# axiom_beta_sensor_cmv12000_v0_12_53e8c18.net
KiCad netlist of a schematic drawn in EAGLE
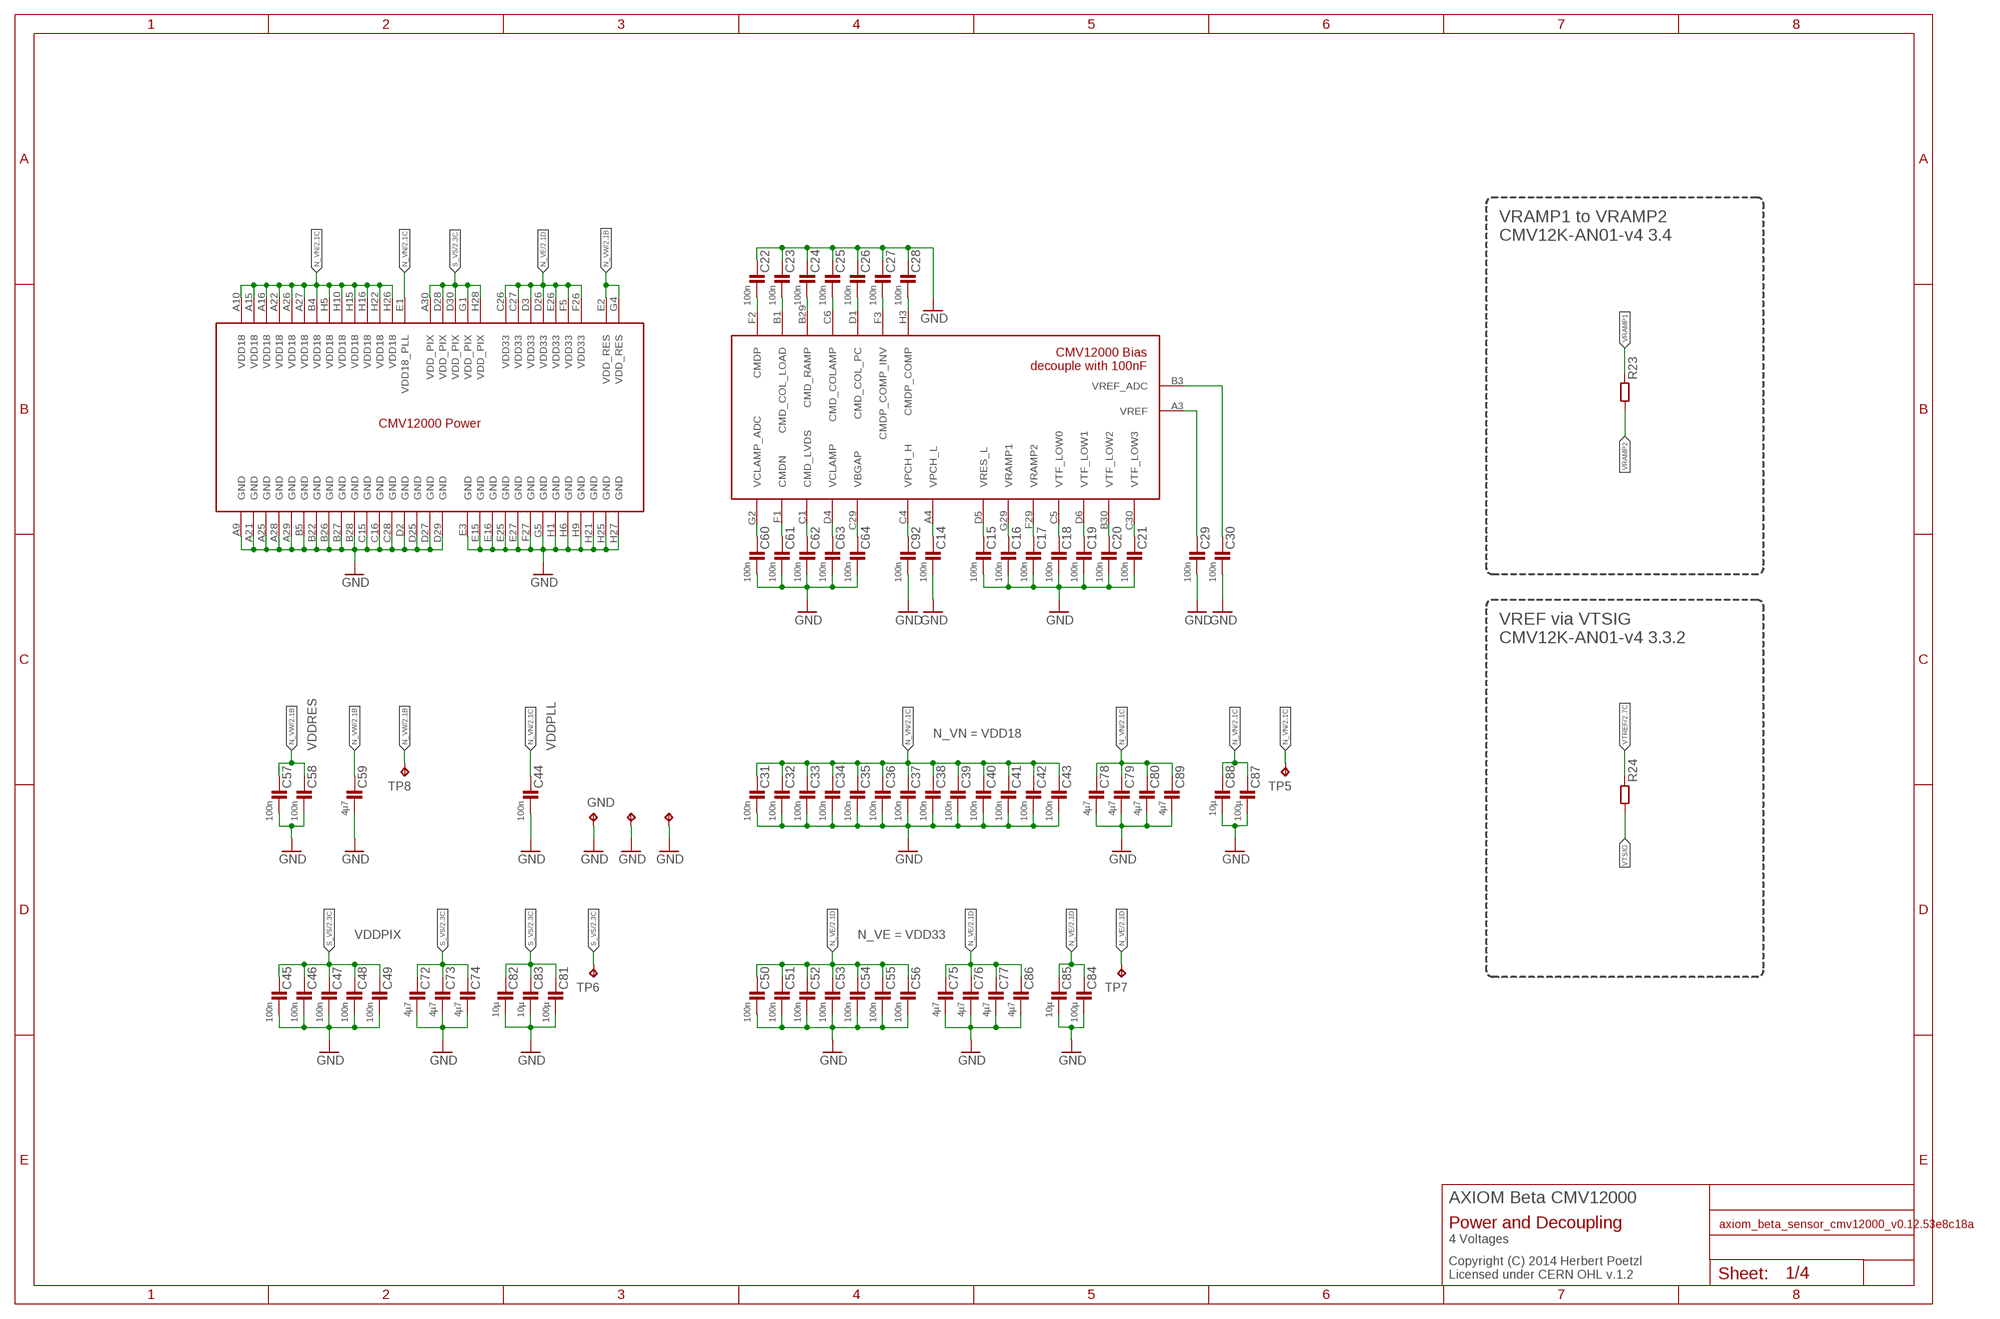
[diagram p0: schematic, sheet 1]
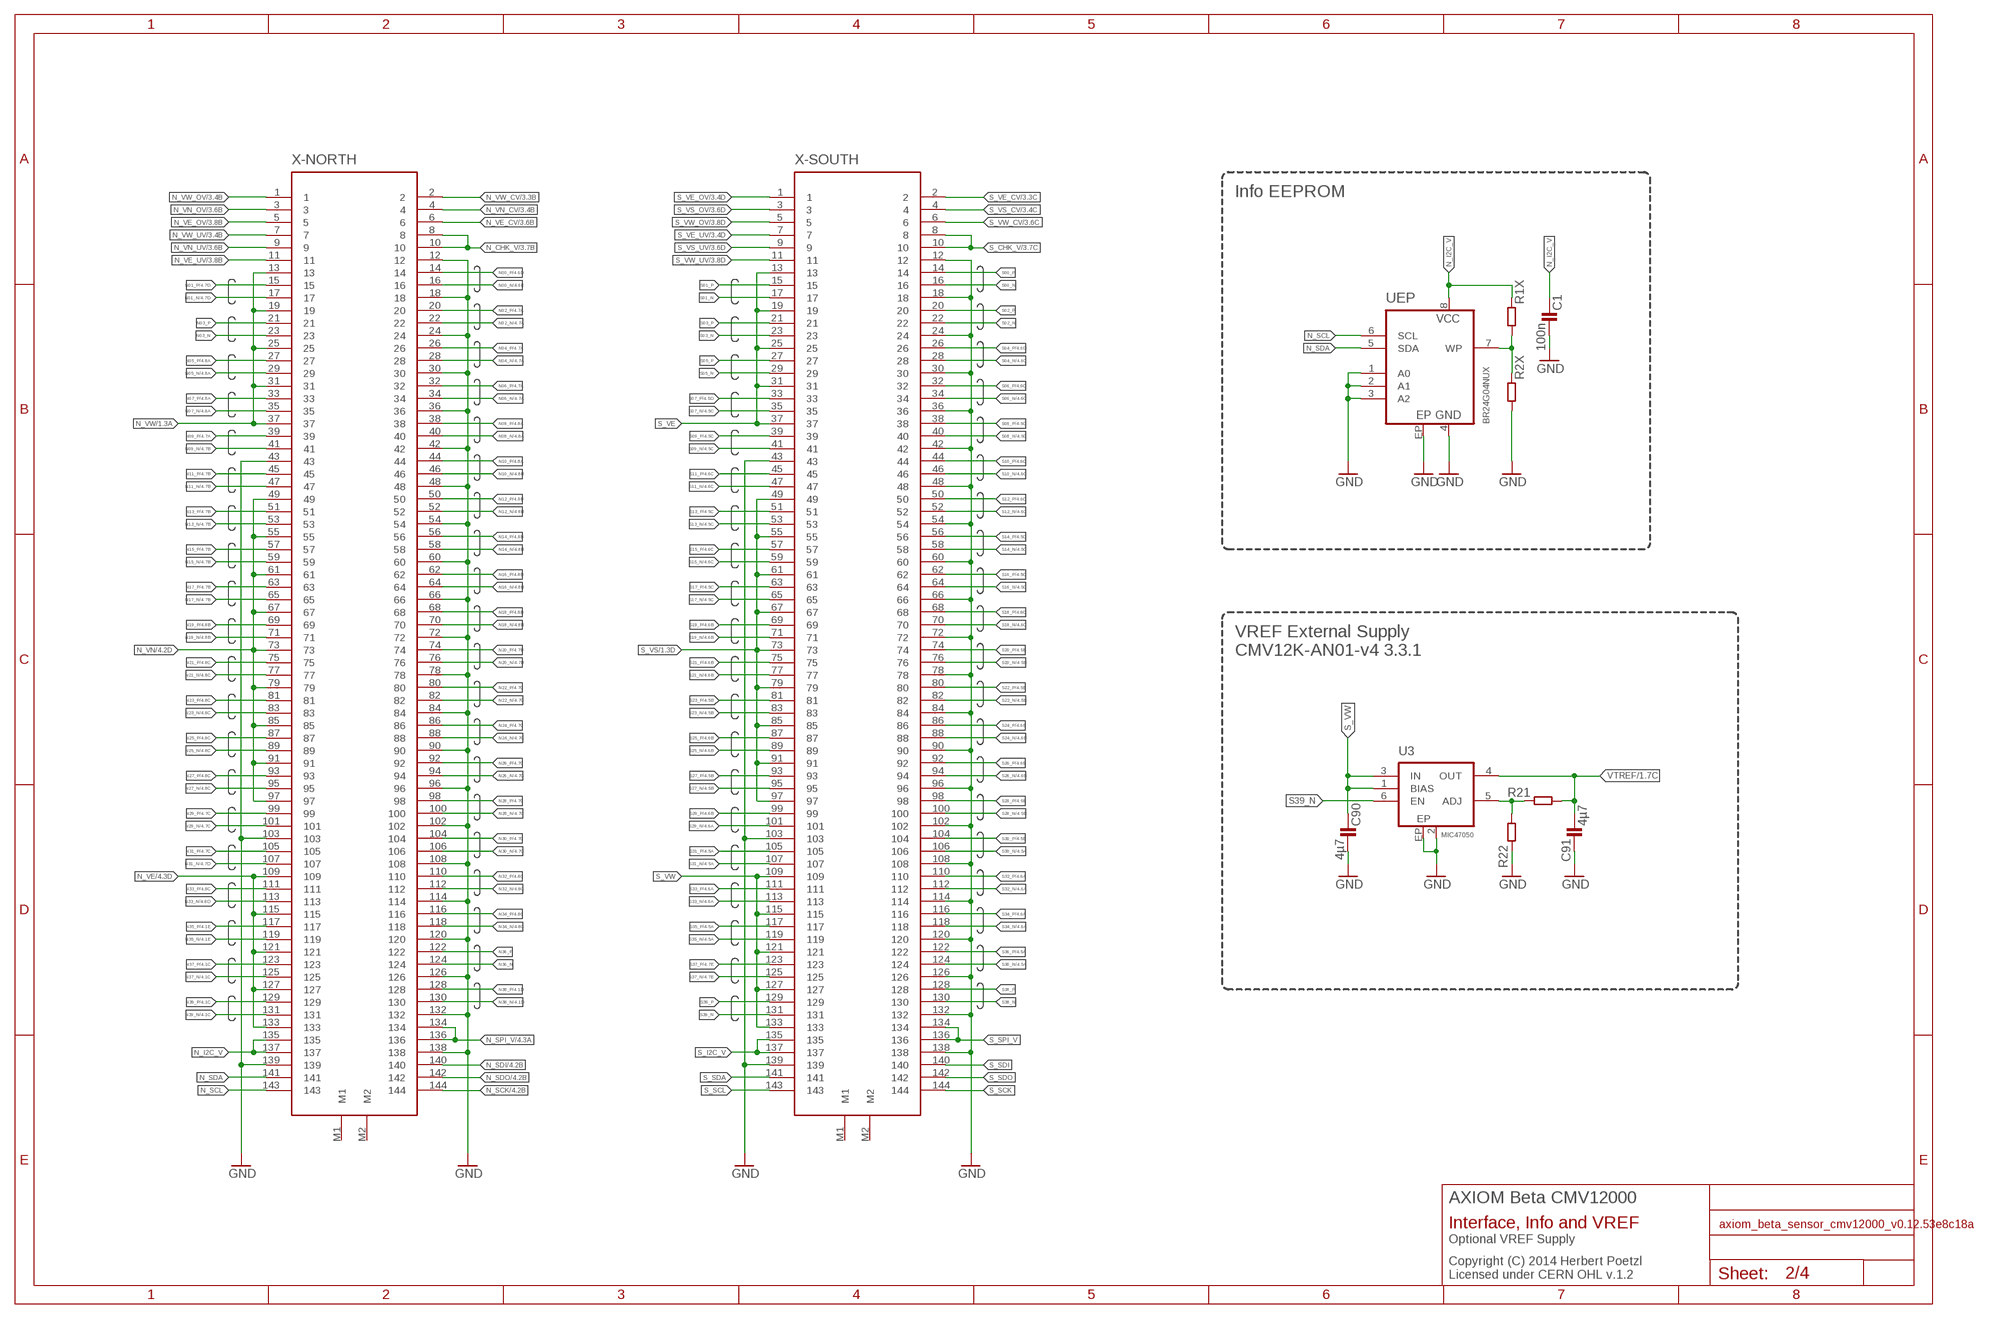
[diagram p1: schematic, sheet 2]
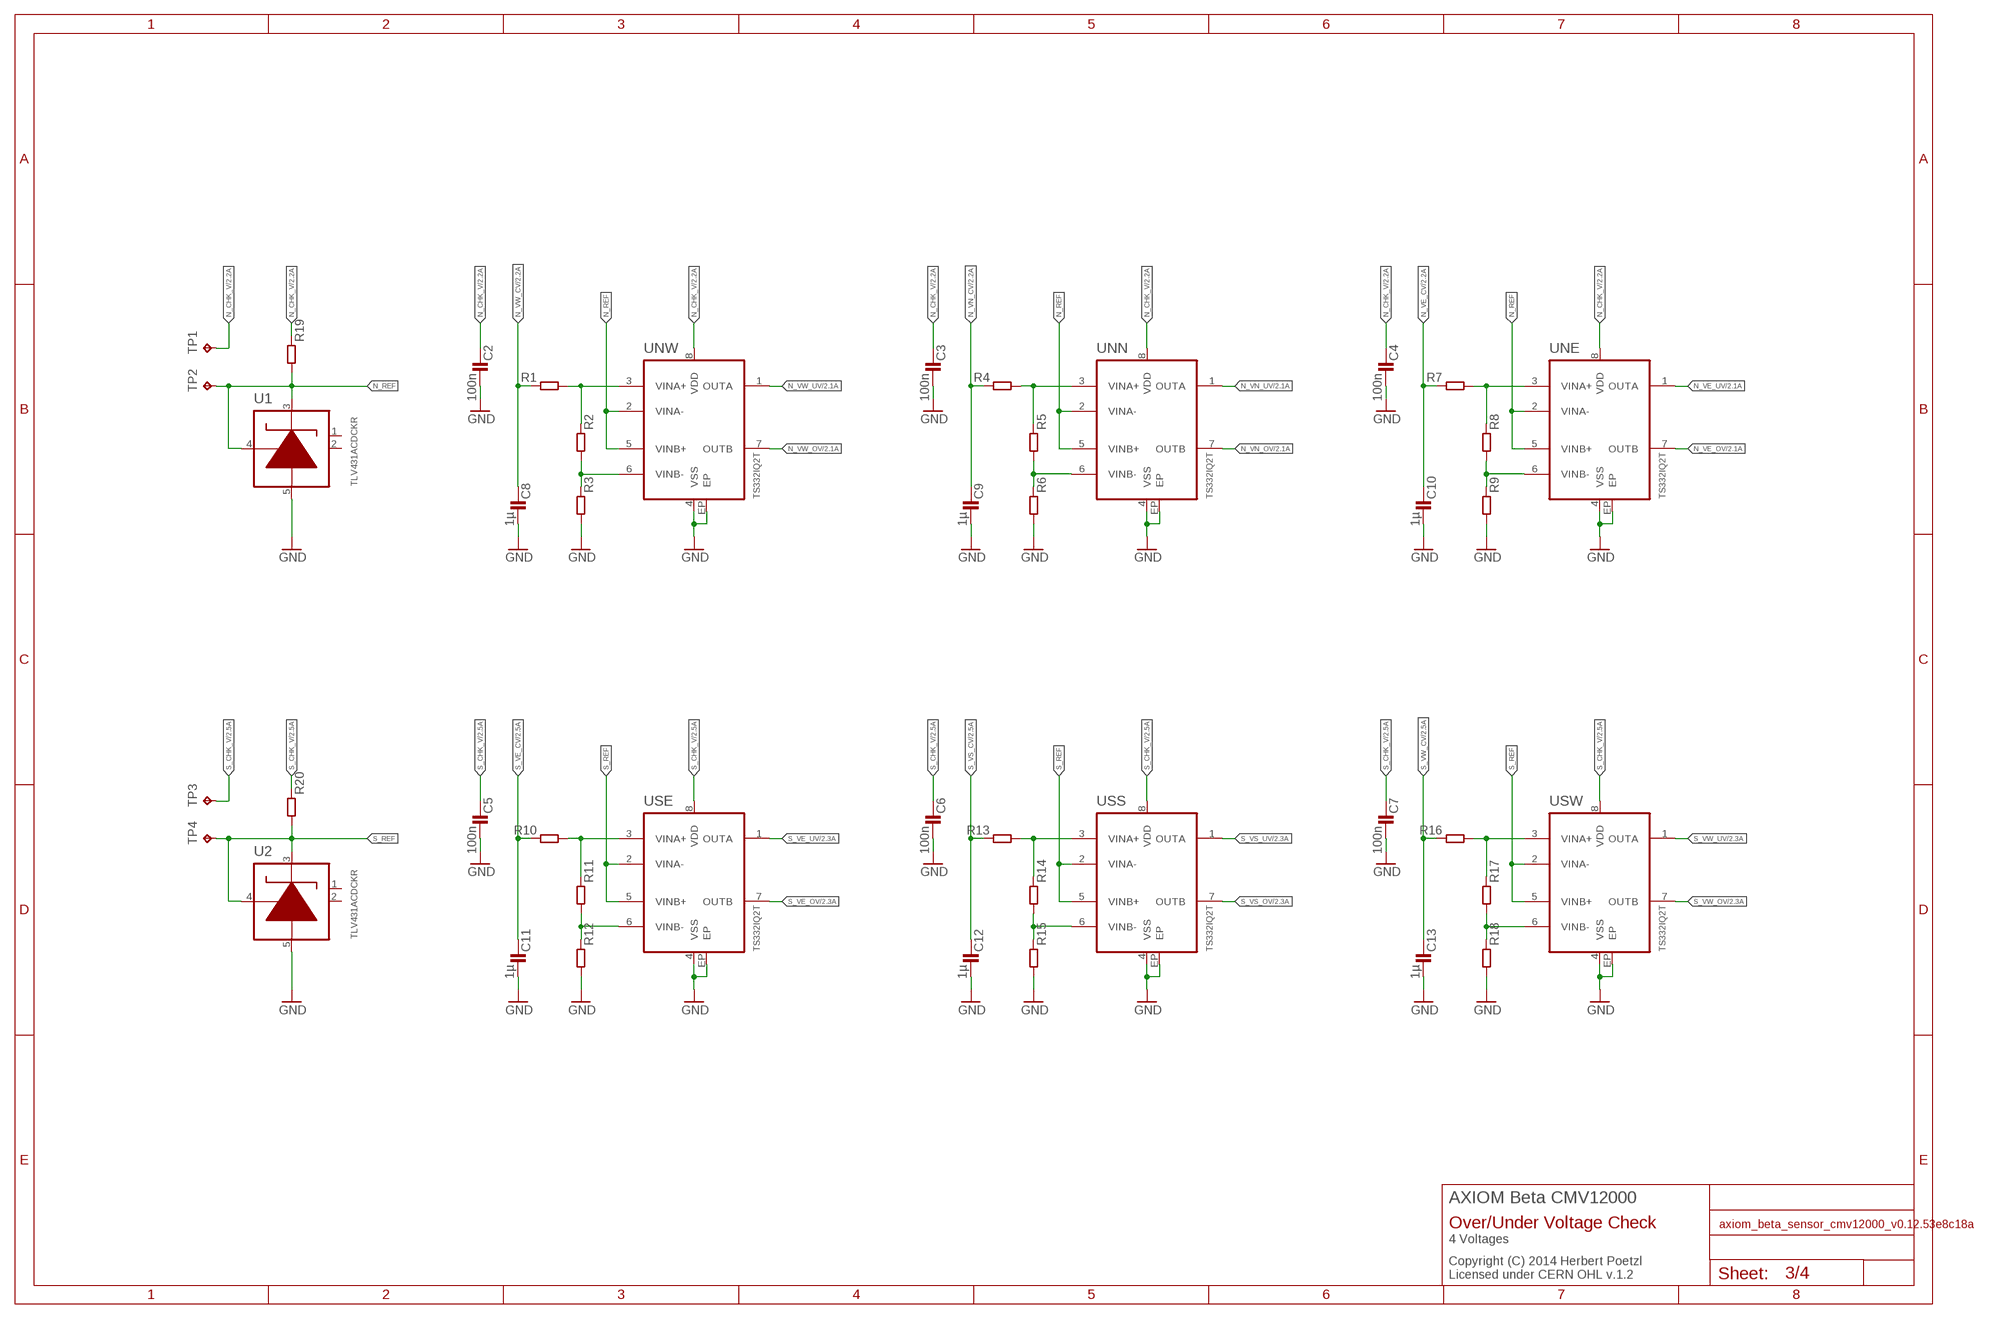
[diagram p2: schematic, sheet 3]
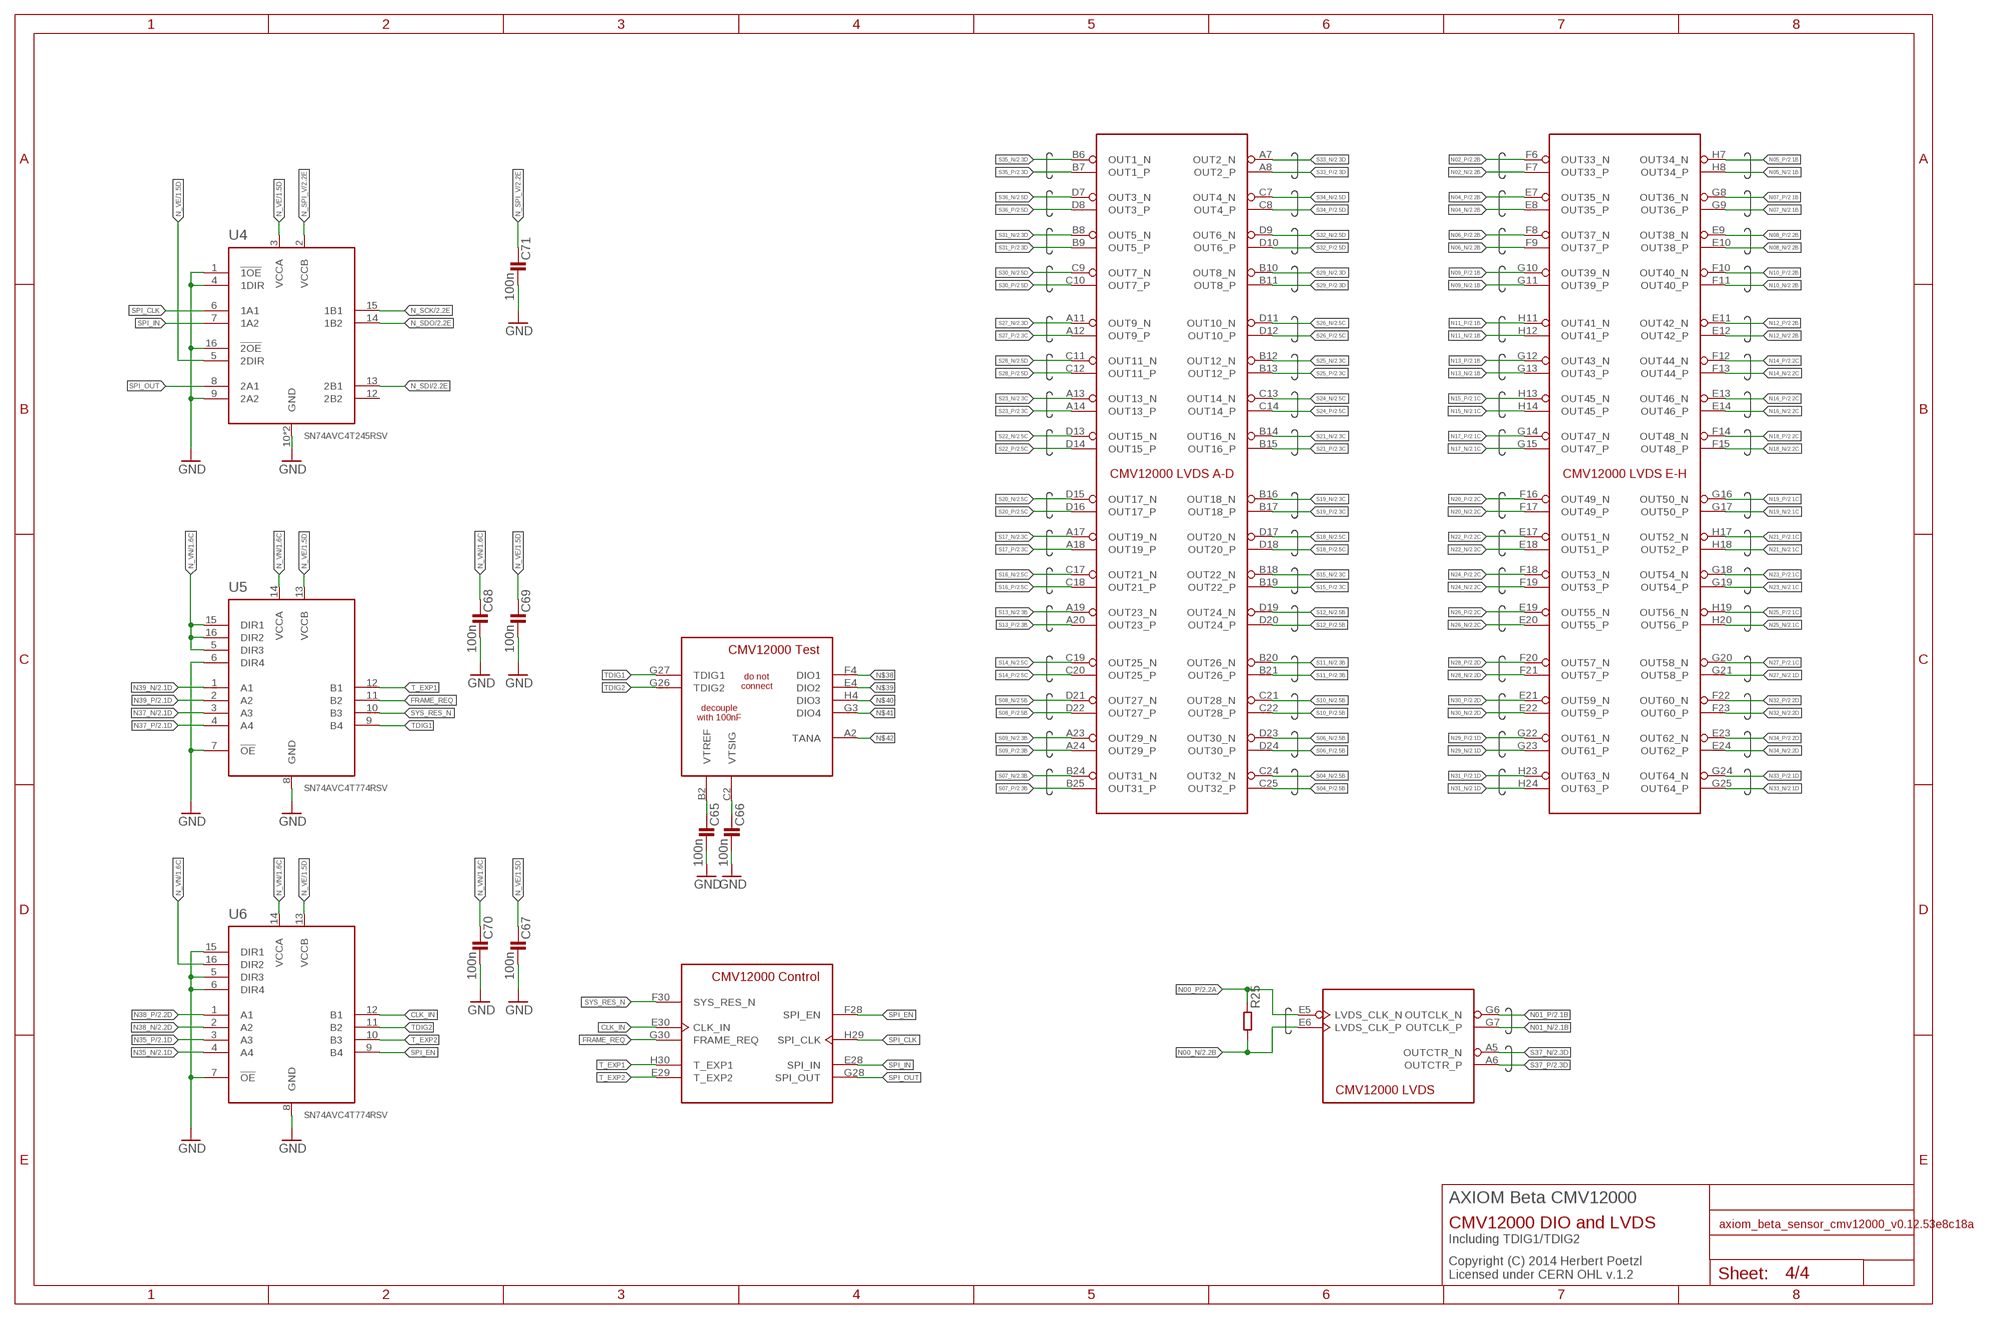
[diagram p3: schematic, sheet 4]

(export (version "E")
  (design (tool "Eeschema 10.0.6"))
  (components
    (comp (ref "C14")
      (value "100n")
      (footprint "eagle-import:0402-C")
      (libsource (lib "eagle-import") (part "C0402-C"))
    )
    (comp (ref "C15")
      (value "100n")
      (footprint "eagle-import:0402-C")
      (libsource (lib "eagle-import") (part "C0402-C"))
    )
    (comp (ref "C16")
      (value "100n")
      (footprint "eagle-import:0402-C")
      (libsource (lib "eagle-import") (part "C0402-C"))
    )
    (comp (ref "C17")
      (value "100n")
      (footprint "eagle-import:0402-C")
      (libsource (lib "eagle-import") (part "C0402-C"))
    )
    (comp (ref "C18")
      (value "100n")
      (footprint "eagle-import:0402-C")
      (libsource (lib "eagle-import") (part "C0402-C"))
    )
    (comp (ref "C19")
      (value "100n")
      (footprint "eagle-import:0402-C")
      (libsource (lib "eagle-import") (part "C0402-C"))
    )
    (comp (ref "C20")
      (value "100n")
      (footprint "eagle-import:0402-C")
      (libsource (lib "eagle-import") (part "C0402-C"))
    )
    (comp (ref "C21")
      (value "100n")
      (footprint "eagle-import:0402-C")
      (libsource (lib "eagle-import") (part "C0402-C"))
    )
    (comp (ref "C22")
      (value "100n")
      (footprint "eagle-import:0402-C")
      (libsource (lib "eagle-import") (part "C0402-C"))
    )
    (comp (ref "C23")
      (value "100n")
      (footprint "eagle-import:0402-C")
      (libsource (lib "eagle-import") (part "C0402-C"))
    )
    (comp (ref "C24")
      (value "100n")
      (footprint "eagle-import:0402-C")
      (libsource (lib "eagle-import") (part "C0402-C"))
    )
    (comp (ref "C25")
      (value "100n")
      (footprint "eagle-import:0402-C")
      (libsource (lib "eagle-import") (part "C0402-C"))
    )
    (comp (ref "C26")
      (value "100n")
      (footprint "eagle-import:0402-C")
      (libsource (lib "eagle-import") (part "C0402-C"))
    )
    (comp (ref "C27")
      (value "100n")
      (footprint "eagle-import:0402-C")
      (libsource (lib "eagle-import") (part "C0402-C"))
    )
    (comp (ref "C28")
      (value "100n")
      (footprint "eagle-import:0402-C")
      (libsource (lib "eagle-import") (part "C0402-C"))
    )
    (comp (ref "C29")
      (value "100n")
      (footprint "eagle-import:0402-C")
      (libsource (lib "eagle-import") (part "C0402-C"))
    )
    (comp (ref "C30")
      (value "100n")
      (footprint "eagle-import:0402-C")
      (libsource (lib "eagle-import") (part "C0402-C"))
    )
    (comp (ref "C31")
      (value "100n")
      (footprint "eagle-import:0402-C")
      (libsource (lib "eagle-import") (part "C0402-C"))
    )
    (comp (ref "C32")
      (value "100n")
      (footprint "eagle-import:0402-C")
      (libsource (lib "eagle-import") (part "C0402-C"))
    )
    (comp (ref "C33")
      (value "100n")
      (footprint "eagle-import:0402-C")
      (libsource (lib "eagle-import") (part "C0402-C"))
    )
    (comp (ref "C34")
      (value "100n")
      (footprint "eagle-import:0402-C")
      (libsource (lib "eagle-import") (part "C0402-C"))
    )
    (comp (ref "C35")
      (value "100n")
      (footprint "eagle-import:0402-C")
      (libsource (lib "eagle-import") (part "C0402-C"))
    )
    (comp (ref "C36")
      (value "100n")
      (footprint "eagle-import:0402-C")
      (libsource (lib "eagle-import") (part "C0402-C"))
    )
    (comp (ref "C37")
      (value "100n")
      (footprint "eagle-import:0402-C")
      (libsource (lib "eagle-import") (part "C0402-C"))
    )
    (comp (ref "C38")
      (value "100n")
      (footprint "eagle-import:0402-C")
      (libsource (lib "eagle-import") (part "C0402-C"))
    )
    (comp (ref "C39")
      (value "100n")
      (footprint "eagle-import:0402-C")
      (libsource (lib "eagle-import") (part "C0402-C"))
    )
    (comp (ref "C40")
      (value "100n")
      (footprint "eagle-import:0402-C")
      (libsource (lib "eagle-import") (part "C0402-C"))
    )
    (comp (ref "C41")
      (value "100n")
      (footprint "eagle-import:0402-C")
      (libsource (lib "eagle-import") (part "C0402-C"))
    )
    (comp (ref "C42")
      (value "100n")
      (footprint "eagle-import:0402-C")
      (libsource (lib "eagle-import") (part "C0402-C"))
    )
    (comp (ref "C43")
      (value "100n")
      (footprint "eagle-import:0402-C")
      (libsource (lib "eagle-import") (part "C0402-C"))
    )
    (comp (ref "C44")
      (value "100n")
      (footprint "eagle-import:0402-C")
      (libsource (lib "eagle-import") (part "C0402-C"))
    )
    (comp (ref "C45")
      (value "100n")
      (footprint "eagle-import:0402-C")
      (libsource (lib "eagle-import") (part "C0402-C"))
    )
    (comp (ref "C46")
      (value "100n")
      (footprint "eagle-import:0402-C")
      (libsource (lib "eagle-import") (part "C0402-C"))
    )
    (comp (ref "C47")
      (value "100n")
      (footprint "eagle-import:0402-C")
      (libsource (lib "eagle-import") (part "C0402-C"))
    )
    (comp (ref "C48")
      (value "100n")
      (footprint "eagle-import:0402-C")
      (libsource (lib "eagle-import") (part "C0402-C"))
    )
    (comp (ref "C49")
      (value "100n")
      (footprint "eagle-import:0402-C")
      (libsource (lib "eagle-import") (part "C0402-C"))
    )
    (comp (ref "C50")
      (value "100n")
      (footprint "eagle-import:0402-C")
      (libsource (lib "eagle-import") (part "C0402-C"))
    )
    (comp (ref "C51")
      (value "100n")
      (footprint "eagle-import:0402-C")
      (libsource (lib "eagle-import") (part "C0402-C"))
    )
    (comp (ref "C52")
      (value "100n")
      (footprint "eagle-import:0402-C")
      (libsource (lib "eagle-import") (part "C0402-C"))
    )
    (comp (ref "C53")
      (value "100n")
      (footprint "eagle-import:0402-C")
      (libsource (lib "eagle-import") (part "C0402-C"))
    )
    (comp (ref "C54")
      (value "100n")
      (footprint "eagle-import:0402-C")
      (libsource (lib "eagle-import") (part "C0402-C"))
    )
    (comp (ref "C55")
      (value "100n")
      (footprint "eagle-import:0402-C")
      (libsource (lib "eagle-import") (part "C0402-C"))
    )
    (comp (ref "C56")
      (value "100n")
      (footprint "eagle-import:0402-C")
      (libsource (lib "eagle-import") (part "C0402-C"))
    )
    (comp (ref "C57")
      (value "100n")
      (footprint "eagle-import:0402-C")
      (libsource (lib "eagle-import") (part "C0402-C"))
    )
    (comp (ref "C58")
      (value "100n")
      (footprint "eagle-import:0402-C")
      (libsource (lib "eagle-import") (part "C0402-C"))
    )
    (comp (ref "C59")
      (value "4µ7")
      (footprint "eagle-import:0402-C")
      (libsource (lib "eagle-import") (part "C0402-C"))
    )
    (comp (ref "C60")
      (value "100n")
      (footprint "eagle-import:0402-C")
      (libsource (lib "eagle-import") (part "C0402-C"))
    )
    (comp (ref "C61")
      (value "100n")
      (footprint "eagle-import:0402-C")
      (libsource (lib "eagle-import") (part "C0402-C"))
    )
    (comp (ref "C62")
      (value "100n")
      (footprint "eagle-import:0402-C")
      (libsource (lib "eagle-import") (part "C0402-C"))
    )
    (comp (ref "C63")
      (value "100n")
      (footprint "eagle-import:0402-C")
      (libsource (lib "eagle-import") (part "C0402-C"))
    )
    (comp (ref "C64")
      (value "100n")
      (footprint "eagle-import:0402-C")
      (libsource (lib "eagle-import") (part "C0402-C"))
    )
    (comp (ref "C72")
      (value "4µ7")
      (footprint "eagle-import:0402-B")
      (libsource (lib "eagle-import") (part "C0402-B"))
    )
    (comp (ref "C73")
      (value "4µ7")
      (footprint "eagle-import:0402-C")
      (libsource (lib "eagle-import") (part "C0402-C"))
    )
    (comp (ref "C74")
      (value "4µ7")
      (footprint "eagle-import:0402-C")
      (libsource (lib "eagle-import") (part "C0402-C"))
    )
    (comp (ref "C75")
      (value "4µ7")
      (footprint "eagle-import:0402-C")
      (libsource (lib "eagle-import") (part "C0402-C"))
    )
    (comp (ref "C76")
      (value "4µ7")
      (footprint "eagle-import:0402-C")
      (libsource (lib "eagle-import") (part "C0402-C"))
    )
    (comp (ref "C77")
      (value "4µ7")
      (footprint "eagle-import:0402-B")
      (libsource (lib "eagle-import") (part "C0402-B"))
    )
    (comp (ref "C78")
      (value "4µ7")
      (footprint "eagle-import:0402-B")
      (libsource (lib "eagle-import") (part "C0402-B"))
    )
    (comp (ref "C79")
      (value "4µ7")
      (footprint "eagle-import:0402-C")
      (libsource (lib "eagle-import") (part "C0402-C"))
    )
    (comp (ref "C80")
      (value "4µ7")
      (footprint "eagle-import:0402-C")
      (libsource (lib "eagle-import") (part "C0402-C"))
    )
    (comp (ref "C81")
      (value "100µ")
      (footprint "eagle-import:1206-B")
      (libsource (lib "eagle-import") (part "C1206-B"))
    )
    (comp (ref "C82")
      (value "10µ")
      (footprint "eagle-import:0603-C")
      (libsource (lib "eagle-import") (part "C0603-C"))
    )
    (comp (ref "C83")
      (value "10µ")
      (footprint "eagle-import:0603-C")
      (libsource (lib "eagle-import") (part "C0603-C"))
    )
    (comp (ref "C84")
      (value "100µ")
      (footprint "eagle-import:1206-B")
      (libsource (lib "eagle-import") (part "C1206-B"))
    )
    (comp (ref "C85")
      (value "10µ")
      (footprint "eagle-import:0603-C")
      (libsource (lib "eagle-import") (part "C0603-C"))
    )
    (comp (ref "C86")
      (value "4µ7")
      (footprint "eagle-import:0402-C")
      (libsource (lib "eagle-import") (part "C0402-C"))
    )
    (comp (ref "C87")
      (value "100µ")
      (footprint "eagle-import:1206-B")
      (libsource (lib "eagle-import") (part "C1206-B"))
    )
    (comp (ref "C88")
      (value "10µ")
      (footprint "eagle-import:0603-C")
      (libsource (lib "eagle-import") (part "C0603-C"))
    )
    (comp (ref "C89")
      (value "4µ7")
      (footprint "eagle-import:0402-C")
      (libsource (lib "eagle-import") (part "C0402-C"))
    )
    (comp (ref "C92")
      (value "100n")
      (footprint "eagle-import:0402-C")
      (libsource (lib "eagle-import") (part "C0402-C"))
    )
    (comp (ref "GND")
      (value "TPTP10R")
      (footprint "eagle-import:TP10R")
      (libsource (lib "eagle-import") (part "TPTP10R"))
    )
    (comp (ref "GND75")
      (value "TPTP10R")
      (footprint "eagle-import:TP10R")
      (libsource (lib "eagle-import") (part "TPTP10R"))
    )
    (comp (ref "GND77")
      (value "TPTP10R")
      (footprint "eagle-import:TP10R")
      (libsource (lib "eagle-import") (part "TPTP10R"))
    )
    (comp (ref "R23")
      (value "R0402-C")
      (footprint "eagle-import:0402-C")
      (libsource (lib "eagle-import") (part "R0402-C"))
    )
    (comp (ref "R24")
      (value "R0402-C")
      (footprint "eagle-import:0402-C")
      (libsource (lib "eagle-import") (part "R0402-C"))
    )
    (comp (ref "SENSOR")
      (value "CMV12000ANDON")
      (footprint "eagle-import:10-30-07-237-400T4")
      (libsource (lib "eagle-import") (part "CMV12000ANDON"))
    )
    (comp (ref "TP5")
      (value "TPTP10R")
      (footprint "eagle-import:TP10R")
      (libsource (lib "eagle-import") (part "TPTP10R"))
    )
    (comp (ref "TP6")
      (value "TPTP10R")
      (footprint "eagle-import:TP10R")
      (libsource (lib "eagle-import") (part "TPTP10R"))
    )
    (comp (ref "TP7")
      (value "TPTP10R")
      (footprint "eagle-import:TP10R")
      (libsource (lib "eagle-import") (part "TPTP10R"))
    )
    (comp (ref "TP8")
      (value "TPTP10R")
      (footprint "eagle-import:TP10R")
      (libsource (lib "eagle-import") (part "TPTP10R"))
    )
    (comp (ref "C65")
      (value "100n")
      (footprint "eagle-import:0402-C")
      (libsource (lib "eagle-import") (part "C0402-C"))
    )
    (comp (ref "C66")
      (value "100n")
      (footprint "eagle-import:0402-C")
      (libsource (lib "eagle-import") (part "C0402-C"))
    )
    (comp (ref "C67")
      (value "100n")
      (footprint "eagle-import:0402-C")
      (libsource (lib "eagle-import") (part "C0402-C"))
    )
    (comp (ref "C68")
      (value "100n")
      (footprint "eagle-import:0402-C")
      (libsource (lib "eagle-import") (part "C0402-C"))
    )
    (comp (ref "C69")
      (value "100n")
      (footprint "eagle-import:0402-C")
      (libsource (lib "eagle-import") (part "C0402-C"))
    )
    (comp (ref "C70")
      (value "100n")
      (footprint "eagle-import:0402-C")
      (libsource (lib "eagle-import") (part "C0402-C"))
    )
    (comp (ref "C71")
      (value "100n")
      (footprint "eagle-import:0402-C")
      (libsource (lib "eagle-import") (part "C0402-C"))
    )
    (comp (ref "R25")
      (value "R0402-C")
      (footprint "eagle-import:0402-C")
      (libsource (lib "eagle-import") (part "R0402-C"))
    )
    (comp (ref "U4")
      (value "SN74AVC4T245RSV")
      (footprint "eagle-import:QFN40P185X265X55-16N")
      (libsource (lib "eagle-import") (part "SN74AVC4T245RSV"))
    )
    (comp (ref "U5")
      (value "SN74AVC4T774RSV")
      (footprint "eagle-import:QFN40P185X265X55-16N")
      (libsource (lib "eagle-import") (part "SN74AVC4T774RSV"))
    )
    (comp (ref "U6")
      (value "SN74AVC4T774RSV")
      (footprint "eagle-import:QFN40P185X265X55-16N")
      (libsource (lib "eagle-import") (part "SN74AVC4T774RSV"))
    )
    (comp (ref "C1")
      (value "100n")
      (footprint "eagle-import:0402-C")
      (libsource (lib "eagle-import") (part "C0402-C"))
    )
    (comp (ref "C90")
      (value "4µ7")
      (footprint "eagle-import:0402-C")
      (libsource (lib "eagle-import") (part "C0402-C"))
    )
    (comp (ref "C91")
      (value "4µ7")
      (footprint "eagle-import:0402-C")
      (libsource (lib "eagle-import") (part "C0402-C"))
    )
    (comp (ref "R1X")
      (value "R0402-C")
      (footprint "eagle-import:0402-C")
      (libsource (lib "eagle-import") (part "R0402-C"))
    )
    (comp (ref "R2X")
      (value "R0402-C")
      (footprint "eagle-import:0402-C")
      (libsource (lib "eagle-import") (part "R0402-C"))
    )
    (comp (ref "R21")
      (value "R0402-C")
      (footprint "eagle-import:0402-C")
      (libsource (lib "eagle-import") (part "R0402-C"))
    )
    (comp (ref "R22")
      (value "R0402-C")
      (footprint "eagle-import:0402-C")
      (libsource (lib "eagle-import") (part "R0402-C"))
    )
    (comp (ref "U3")
      (value "MIC47050")
      (footprint "eagle-import:MLF-6")
      (libsource (lib "eagle-import") (part "MIC47050-ADJ"))
    )
    (comp (ref "UEP")
      (value "BR24G04NUX")
      (footprint "eagle-import:DFN200X300X100-9N")
      (libsource (lib "eagle-import") (part "BR24G04NUX"))
    )
    (comp (ref "X-NORTH")
      (value "FX10-144P")
      (footprint "eagle-import:FX10A-144P")
      (libsource (lib "eagle-import") (part "FX10-144P"))
    )
    (comp (ref "X-SOUTH")
      (value "FX10-144P")
      (footprint "eagle-import:FX10A-144P")
      (libsource (lib "eagle-import") (part "FX10-144P"))
    )
    (comp (ref "C2")
      (value "100n")
      (footprint "eagle-import:0402-C")
      (libsource (lib "eagle-import") (part "C0402-C"))
    )
    (comp (ref "C3")
      (value "100n")
      (footprint "eagle-import:0402-C")
      (libsource (lib "eagle-import") (part "C0402-C"))
    )
    (comp (ref "C4")
      (value "100n")
      (footprint "eagle-import:0402-C")
      (libsource (lib "eagle-import") (part "C0402-C"))
    )
    (comp (ref "C5")
      (value "100n")
      (footprint "eagle-import:0402-C")
      (libsource (lib "eagle-import") (part "C0402-C"))
    )
    (comp (ref "C6")
      (value "100n")
      (footprint "eagle-import:0402-C")
      (libsource (lib "eagle-import") (part "C0402-C"))
    )
    (comp (ref "C7")
      (value "100n")
      (footprint "eagle-import:0402-C")
      (libsource (lib "eagle-import") (part "C0402-C"))
    )
    (comp (ref "C8")
      (value "1µ")
      (footprint "eagle-import:0402-C")
      (libsource (lib "eagle-import") (part "C0402-C"))
    )
    (comp (ref "C9")
      (value "1µ")
      (footprint "eagle-import:0402-C")
      (libsource (lib "eagle-import") (part "C0402-C"))
    )
    (comp (ref "C10")
      (value "1µ")
      (footprint "eagle-import:0402-C")
      (libsource (lib "eagle-import") (part "C0402-C"))
    )
    (comp (ref "C11")
      (value "1µ")
      (footprint "eagle-import:0402-C")
      (libsource (lib "eagle-import") (part "C0402-C"))
    )
    (comp (ref "C12")
      (value "1µ")
      (footprint "eagle-import:0402-C")
      (libsource (lib "eagle-import") (part "C0402-C"))
    )
    (comp (ref "C13")
      (value "1µ")
      (footprint "eagle-import:0402-C")
      (libsource (lib "eagle-import") (part "C0402-C"))
    )
    (comp (ref "R1")
      (value "R0402-C")
      (footprint "eagle-import:0402-C")
      (libsource (lib "eagle-import") (part "R0402-C"))
    )
    (comp (ref "R2")
      (value "R0402-C")
      (footprint "eagle-import:0402-C")
      (libsource (lib "eagle-import") (part "R0402-C"))
    )
    (comp (ref "R3")
      (value "R0402-C")
      (footprint "eagle-import:0402-C")
      (libsource (lib "eagle-import") (part "R0402-C"))
    )
    (comp (ref "R4")
      (value "R0402-C")
      (footprint "eagle-import:0402-C")
      (libsource (lib "eagle-import") (part "R0402-C"))
    )
    (comp (ref "R5")
      (value "R0402-C")
      (footprint "eagle-import:0402-C")
      (libsource (lib "eagle-import") (part "R0402-C"))
    )
    (comp (ref "R6")
      (value "R0402-C")
      (footprint "eagle-import:0402-C")
      (libsource (lib "eagle-import") (part "R0402-C"))
    )
    (comp (ref "R7")
      (value "R0402-C")
      (footprint "eagle-import:0402-C")
      (libsource (lib "eagle-import") (part "R0402-C"))
    )
    (comp (ref "R8")
      (value "R0402-C")
      (footprint "eagle-import:0402-C")
      (libsource (lib "eagle-import") (part "R0402-C"))
    )
    (comp (ref "R9")
      (value "R0402-C")
      (footprint "eagle-import:0402-C")
      (libsource (lib "eagle-import") (part "R0402-C"))
    )
    (comp (ref "R10")
      (value "R0402-C")
      (footprint "eagle-import:0402-C")
      (libsource (lib "eagle-import") (part "R0402-C"))
    )
    (comp (ref "R11")
      (value "R0402-C")
      (footprint "eagle-import:0402-C")
      (libsource (lib "eagle-import") (part "R0402-C"))
    )
    (comp (ref "R12")
      (value "R0402-C")
      (footprint "eagle-import:0402-C")
      (libsource (lib "eagle-import") (part "R0402-C"))
    )
    (comp (ref "R13")
      (value "R0402-C")
      (footprint "eagle-import:0402-C")
      (libsource (lib "eagle-import") (part "R0402-C"))
    )
    (comp (ref "R14")
      (value "R0402-C")
      (footprint "eagle-import:0402-C")
      (libsource (lib "eagle-import") (part "R0402-C"))
    )
    (comp (ref "R15")
      (value "R0402-C")
      (footprint "eagle-import:0402-C")
      (libsource (lib "eagle-import") (part "R0402-C"))
    )
    (comp (ref "R16")
      (value "R0402-C")
      (footprint "eagle-import:0402-C")
      (libsource (lib "eagle-import") (part "R0402-C"))
    )
    (comp (ref "R17")
      (value "R0402-C")
      (footprint "eagle-import:0402-C")
      (libsource (lib "eagle-import") (part "R0402-C"))
    )
    (comp (ref "R18")
      (value "R0402-C")
      (footprint "eagle-import:0402-C")
      (libsource (lib "eagle-import") (part "R0402-C"))
    )
    (comp (ref "R19")
      (value "R0402-C")
      (footprint "eagle-import:0402-C")
      (libsource (lib "eagle-import") (part "R0402-C"))
    )
    (comp (ref "R20")
      (value "R0402-C")
      (footprint "eagle-import:0402-C")
      (libsource (lib "eagle-import") (part "R0402-C"))
    )
    (comp (ref "TP1")
      (value "TPTP10R")
      (footprint "eagle-import:TP10R")
      (libsource (lib "eagle-import") (part "TPTP10R"))
    )
    (comp (ref "TP2")
      (value "TPTP10R")
      (footprint "eagle-import:TP10R")
      (libsource (lib "eagle-import") (part "TPTP10R"))
    )
    (comp (ref "TP3")
      (value "TPTP10R")
      (footprint "eagle-import:TP10R")
      (libsource (lib "eagle-import") (part "TPTP10R"))
    )
    (comp (ref "TP4")
      (value "TPTP10R")
      (footprint "eagle-import:TP10R")
      (libsource (lib "eagle-import") (part "TPTP10R"))
    )
    (comp (ref "U1")
      (value "TLV431ACDCKR")
      (footprint "eagle-import:SOT65P210X110-5N")
      (libsource (lib "eagle-import") (part "TLV431ACDCKR"))
    )
    (comp (ref "U2")
      (value "TLV431ACDCKR")
      (footprint "eagle-import:SOT65P210X110-5N")
      (libsource (lib "eagle-import") (part "TLV431ACDCKR"))
    )
    (comp (ref "UNE")
      (value "TS332IQ2T")
      (footprint "eagle-import:DFN200X200X100-9N")
      (libsource (lib "eagle-import") (part "TS332IQ2T"))
    )
    (comp (ref "UNN")
      (value "TS332IQ2T")
      (footprint "eagle-import:DFN200X200X100-9N")
      (libsource (lib "eagle-import") (part "TS332IQ2T"))
    )
    (comp (ref "UNW")
      (value "TS332IQ2T")
      (footprint "eagle-import:DFN200X200X100-9N")
      (libsource (lib "eagle-import") (part "TS332IQ2T"))
    )
    (comp (ref "USE")
      (value "TS332IQ2T")
      (footprint "eagle-import:DFN200X200X100-9N")
      (libsource (lib "eagle-import") (part "TS332IQ2T"))
    )
    (comp (ref "USS")
      (value "TS332IQ2T")
      (footprint "eagle-import:DFN200X200X100-9N")
      (libsource (lib "eagle-import") (part "TS332IQ2T"))
    )
    (comp (ref "USW")
      (value "TS332IQ2T")
      (footprint "eagle-import:DFN200X200X100-9N")
      (libsource (lib "eagle-import") (part "TS332IQ2T"))
    )
  )
  (nets
    (net (code "1") (name "CLK_IN") (class "Default")
      (node (ref "SENSOR") (pin "E30") (pinfunction "CLK_IN_E30") (pintype "input"))
      (node (ref "U6") (pin "12") (pinfunction "B1_12") (pintype "bidirectional"))
    )
    (net (code "2") (name "FRAME_REQ") (class "Default")
      (node (ref "SENSOR") (pin "G30") (pinfunction "FRAME_REQ_G30") (pintype "input"))
      (node (ref "U5") (pin "11") (pinfunction "B2_11") (pintype "bidirectional"))
    )
    (net (code "3") (name "GND") (class "Default")
      (node (ref "C1") (pin "2") (pinfunction "2_2") (pintype "passive"))
      (node (ref "C10") (pin "2") (pinfunction "2_2") (pintype "passive"))
      (node (ref "C11") (pin "2") (pinfunction "2_2") (pintype "passive"))
      (node (ref "C12") (pin "2") (pinfunction "2_2") (pintype "passive"))
      (node (ref "C13") (pin "2") (pinfunction "2_2") (pintype "passive"))
      (node (ref "C14") (pin "2") (pinfunction "2_2") (pintype "passive"))
      (node (ref "C15") (pin "2") (pinfunction "2_2") (pintype "passive"))
      (node (ref "C16") (pin "2") (pinfunction "2_2") (pintype "passive"))
      (node (ref "C17") (pin "2") (pinfunction "2_2") (pintype "passive"))
      (node (ref "C18") (pin "2") (pinfunction "2_2") (pintype "passive"))
      (node (ref "C19") (pin "2") (pinfunction "2_2") (pintype "passive"))
      (node (ref "C2") (pin "2") (pinfunction "2_2") (pintype "passive"))
      (node (ref "C20") (pin "2") (pinfunction "2_2") (pintype "passive"))
      (node (ref "C21") (pin "2") (pinfunction "2_2") (pintype "passive"))
      (node (ref "C22") (pin "1") (pinfunction "1_1") (pintype "passive"))
      (node (ref "C23") (pin "1") (pinfunction "1_1") (pintype "passive"))
      (node (ref "C24") (pin "1") (pinfunction "1_1") (pintype "passive"))
      (node (ref "C25") (pin "1") (pinfunction "1_1") (pintype "passive"))
      (node (ref "C26") (pin "1") (pinfunction "1_1") (pintype "passive"))
      (node (ref "C27") (pin "1") (pinfunction "1_1") (pintype "passive"))
      (node (ref "C28") (pin "1") (pinfunction "1_1") (pintype "passive"))
      (node (ref "C29") (pin "2") (pinfunction "2_2") (pintype "passive"))
      (node (ref "C3") (pin "2") (pinfunction "2_2") (pintype "passive"))
      (node (ref "C30") (pin "2") (pinfunction "2_2") (pintype "passive"))
      (node (ref "C31") (pin "2") (pinfunction "2_2") (pintype "passive"))
      (node (ref "C32") (pin "2") (pinfunction "2_2") (pintype "passive"))
      (node (ref "C33") (pin "2") (pinfunction "2_2") (pintype "passive"))
      (node (ref "C34") (pin "2") (pinfunction "2_2") (pintype "passive"))
      (node (ref "C35") (pin "2") (pinfunction "2_2") (pintype "passive"))
      (node (ref "C36") (pin "2") (pinfunction "2_2") (pintype "passive"))
      (node (ref "C37") (pin "2") (pinfunction "2_2") (pintype "passive"))
      (node (ref "C38") (pin "2") (pinfunction "2_2") (pintype "passive"))
      (node (ref "C39") (pin "2") (pinfunction "2_2") (pintype "passive"))
      (node (ref "C4") (pin "2") (pinfunction "2_2") (pintype "passive"))
      (node (ref "C40") (pin "2") (pinfunction "2_2") (pintype "passive"))
      (node (ref "C41") (pin "2") (pinfunction "2_2") (pintype "passive"))
      (node (ref "C42") (pin "2") (pinfunction "2_2") (pintype "passive"))
      (node (ref "C43") (pin "2") (pinfunction "2_2") (pintype "passive"))
      (node (ref "C44") (pin "2") (pinfunction "2_2") (pintype "passive"))
      (node (ref "C45") (pin "2") (pinfunction "2_2") (pintype "passive"))
      (node (ref "C46") (pin "2") (pinfunction "2_2") (pintype "passive"))
      (node (ref "C47") (pin "2") (pinfunction "2_2") (pintype "passive"))
      (node (ref "C48") (pin "2") (pinfunction "2_2") (pintype "passive"))
      (node (ref "C49") (pin "2") (pinfunction "2_2") (pintype "passive"))
      (node (ref "C5") (pin "2") (pinfunction "2_2") (pintype "passive"))
      (node (ref "C50") (pin "2") (pinfunction "2_2") (pintype "passive"))
      (node (ref "C51") (pin "2") (pinfunction "2_2") (pintype "passive"))
      (node (ref "C52") (pin "2") (pinfunction "2_2") (pintype "passive"))
      (node (ref "C53") (pin "2") (pinfunction "2_2") (pintype "passive"))
      (node (ref "C54") (pin "2") (pinfunction "2_2") (pintype "passive"))
      (node (ref "C55") (pin "2") (pinfunction "2_2") (pintype "passive"))
      (node (ref "C56") (pin "2") (pinfunction "2_2") (pintype "passive"))
      (node (ref "C57") (pin "2") (pinfunction "2_2") (pintype "passive"))
      (node (ref "C58") (pin "2") (pinfunction "2_2") (pintype "passive"))
      (node (ref "C59") (pin "2") (pinfunction "2_2") (pintype "passive"))
      (node (ref "C6") (pin "2") (pinfunction "2_2") (pintype "passive"))
      (node (ref "C60") (pin "2") (pinfunction "2_2") (pintype "passive"))
      (node (ref "C61") (pin "2") (pinfunction "2_2") (pintype "passive"))
      (node (ref "C62") (pin "2") (pinfunction "2_2") (pintype "passive"))
      (node (ref "C63") (pin "2") (pinfunction "2_2") (pintype "passive"))
      (node (ref "C64") (pin "2") (pinfunction "2_2") (pintype "passive"))
      (node (ref "C65") (pin "2") (pinfunction "2_2") (pintype "passive"))
      (node (ref "C66") (pin "2") (pinfunction "2_2") (pintype "passive"))
      (node (ref "C67") (pin "2") (pinfunction "2_2") (pintype "passive"))
      (node (ref "C68") (pin "2") (pinfunction "2_2") (pintype "passive"))
      (node (ref "C69") (pin "2") (pinfunction "2_2") (pintype "passive"))
      (node (ref "C7") (pin "2") (pinfunction "2_2") (pintype "passive"))
      (node (ref "C70") (pin "2") (pinfunction "2_2") (pintype "passive"))
      (node (ref "C71") (pin "2") (pinfunction "2_2") (pintype "passive"))
      (node (ref "C72") (pin "2") (pinfunction "2_2") (pintype "passive"))
      (node (ref "C73") (pin "2") (pinfunction "2_2") (pintype "passive"))
      (node (ref "C74") (pin "2") (pinfunction "2_2") (pintype "passive"))
      (node (ref "C75") (pin "2") (pinfunction "2_2") (pintype "passive"))
      (node (ref "C76") (pin "2") (pinfunction "2_2") (pintype "passive"))
      (node (ref "C77") (pin "2") (pinfunction "2_2") (pintype "passive"))
      (node (ref "C78") (pin "2") (pinfunction "2_2") (pintype "passive"))
      (node (ref "C79") (pin "2") (pinfunction "2_2") (pintype "passive"))
      (node (ref "C8") (pin "2") (pinfunction "2_2") (pintype "passive"))
      (node (ref "C80") (pin "2") (pinfunction "2_2") (pintype "passive"))
      (node (ref "C81") (pin "2") (pinfunction "2_2") (pintype "passive"))
      (node (ref "C82") (pin "2") (pinfunction "2_2") (pintype "passive"))
      (node (ref "C83") (pin "2") (pinfunction "2_2") (pintype "passive"))
      (node (ref "C84") (pin "2") (pinfunction "2_2") (pintype "passive"))
      (node (ref "C85") (pin "2") (pinfunction "2_2") (pintype "passive"))
      (node (ref "C86") (pin "2") (pinfunction "2_2") (pintype "passive"))
      (node (ref "C87") (pin "2") (pinfunction "2_2") (pintype "passive"))
      (node (ref "C88") (pin "2") (pinfunction "2_2") (pintype "passive"))
      (node (ref "C89") (pin "2") (pinfunction "2_2") (pintype "passive"))
      (node (ref "C9") (pin "2") (pinfunction "2_2") (pintype "passive"))
      (node (ref "C90") (pin "2") (pinfunction "2_2") (pintype "passive"))
      (node (ref "C91") (pin "1") (pinfunction "1_1") (pintype "passive"))
      (node (ref "C92") (pin "2") (pinfunction "2_2") (pintype "passive"))
      (node (ref "GND") (pin "TP") (pinfunction "TP_TP") (pintype "input"))
      (node (ref "GND75") (pin "TP") (pinfunction "TP_TP") (pintype "input"))
      (node (ref "GND77") (pin "TP") (pinfunction "TP_TP") (pintype "input"))
      (node (ref "R12") (pin "2") (pinfunction "2_2") (pintype "passive"))
      (node (ref "R15") (pin "2") (pinfunction "2_2") (pintype "passive"))
      (node (ref "R18") (pin "2") (pinfunction "2_2") (pintype "passive"))
      (node (ref "R22") (pin "1") (pinfunction "1_1") (pintype "passive"))
      (node (ref "R2X") (pin "2") (pinfunction "2_2") (pintype "passive"))
      (node (ref "R3") (pin "2") (pinfunction "2_2") (pintype "passive"))
      (node (ref "R6") (pin "2") (pinfunction "2_2") (pintype "passive"))
      (node (ref "R9") (pin "2") (pinfunction "2_2") (pintype "passive"))
      (node (ref "SENSOR") (pin "A21") (pinfunction "GND_A21") (pintype "power_in"))
      (node (ref "SENSOR") (pin "A25") (pinfunction "GND_A25") (pintype "power_in"))
      (node (ref "SENSOR") (pin "A28") (pinfunction "GND_A28") (pintype "power_in"))
      (node (ref "SENSOR") (pin "A29") (pinfunction "GND_A29") (pintype "power_in"))
      (node (ref "SENSOR") (pin "A9") (pinfunction "GND_A9") (pintype "power_in"))
      (node (ref "SENSOR") (pin "B22") (pinfunction "GND_B22") (pintype "power_in"))
      (node (ref "SENSOR") (pin "B26") (pinfunction "GND_B26") (pintype "power_in"))
      (node (ref "SENSOR") (pin "B27") (pinfunction "GND_B27") (pintype "power_in"))
      (node (ref "SENSOR") (pin "B28") (pinfunction "GND_B28") (pintype "power_in"))
      (node (ref "SENSOR") (pin "B5") (pinfunction "GND_B5") (pintype "power_in"))
      (node (ref "SENSOR") (pin "C15") (pinfunction "GND_C15") (pintype "power_in"))
      (node (ref "SENSOR") (pin "C16") (pinfunction "GND_C16") (pintype "power_in"))
      (node (ref "SENSOR") (pin "C28") (pinfunction "GND_C28") (pintype "power_in"))
      (node (ref "SENSOR") (pin "D2") (pinfunction "GND_D2") (pintype "power_in"))
      (node (ref "SENSOR") (pin "D25") (pinfunction "GND_D25") (pintype "power_in"))
      (node (ref "SENSOR") (pin "D27") (pinfunction "GND_D27") (pintype "power_in"))
      (node (ref "SENSOR") (pin "D29") (pinfunction "GND_D29") (pintype "power_in"))
      (node (ref "SENSOR") (pin "E15") (pinfunction "GND_E15") (pintype "power_in"))
      (node (ref "SENSOR") (pin "E16") (pinfunction "GND_E16") (pintype "power_in"))
      (node (ref "SENSOR") (pin "E25") (pinfunction "GND_E25") (pintype "power_in"))
      (node (ref "SENSOR") (pin "E27") (pinfunction "GND_E27") (pintype "power_in"))
      (node (ref "SENSOR") (pin "E3") (pinfunction "GND_E3") (pintype "power_in"))
      (node (ref "SENSOR") (pin "F27") (pinfunction "GND_F27") (pintype "power_in"))
      (node (ref "SENSOR") (pin "G5") (pinfunction "GND_G5") (pintype "power_in"))
      (node (ref "SENSOR") (pin "H1") (pinfunction "GND_H1") (pintype "power_in"))
      (node (ref "SENSOR") (pin "H21") (pinfunction "GND_H21") (pintype "power_in"))
      (node (ref "SENSOR") (pin "H25") (pinfunction "GND_H25") (pintype "power_in"))
      (node (ref "SENSOR") (pin "H27") (pinfunction "GND_H27") (pintype "power_in"))
      (node (ref "SENSOR") (pin "H6") (pinfunction "GND_H6") (pintype "power_in"))
      (node (ref "SENSOR") (pin "H9") (pinfunction "GND_H9") (pintype "power_in"))
      (node (ref "U1") (pin "5") (pinfunction "ANODE_5") (pintype "input"))
      (node (ref "U2") (pin "5") (pinfunction "ANODE_5") (pintype "input"))
      (node (ref "U3") (pin "2") (pinfunction "GND_2") (pintype "power_in"))
      (node (ref "U3") (pin "EP") (pinfunction "EP_EP") (pintype "power_in"))
      (node (ref "U4") (pin "1") (pinfunction "~{1OE}_1") (pintype "input"))
      (node (ref "U4") (pin "10") (pinfunction "GND_10") (pintype "passive"))
      (node (ref "U4") (pin "11") (pinfunction "GND_11") (pintype "passive"))
      (node (ref "U4") (pin "16") (pinfunction "~{2OE}_16") (pintype "input"))
      (node (ref "U4") (pin "4") (pinfunction "1DIR_4") (pintype "input"))
      (node (ref "U4") (pin "9") (pinfunction "2A2_9") (pintype "output"))
      (node (ref "U5") (pin "6") (pinfunction "DIR4_6") (pintype "input"))
      (node (ref "U5") (pin "7") (pinfunction "~{OE}_7") (pintype "input"))
      (node (ref "U5") (pin "8") (pinfunction "GND_8") (pintype "passive"))
      (node (ref "U6") (pin "15") (pinfunction "DIR1_15") (pintype "input"))
      (node (ref "U6") (pin "5") (pinfunction "DIR3_5") (pintype "input"))
      (node (ref "U6") (pin "6") (pinfunction "DIR4_6") (pintype "input"))
      (node (ref "U6") (pin "7") (pinfunction "~{OE}_7") (pintype "input"))
      (node (ref "U6") (pin "8") (pinfunction "GND_8") (pintype "passive"))
      (node (ref "UEP") (pin "1") (pinfunction "A0_1") (pintype "input"))
      (node (ref "UEP") (pin "2") (pinfunction "A1_2") (pintype "input"))
      (node (ref "UEP") (pin "3") (pinfunction "A2_3") (pintype "input"))
      (node (ref "UEP") (pin "4") (pinfunction "GND_4") (pintype "passive"))
      (node (ref "UEP") (pin "EP") (pinfunction "EP_EP") (pintype "passive"))
      (node (ref "UNE") (pin "4") (pinfunction "VSS_4") (pintype "power_in"))
      (node (ref "UNE") (pin "EP") (pinfunction "EP_EP") (pintype "passive"))
      (node (ref "UNN") (pin "4") (pinfunction "VSS_4") (pintype "power_in"))
      (node (ref "UNN") (pin "EP") (pinfunction "EP_EP") (pintype "passive"))
      (node (ref "UNW") (pin "4") (pinfunction "VSS_4") (pintype "power_in"))
      (node (ref "UNW") (pin "EP") (pinfunction "EP_EP") (pintype "passive"))
      (node (ref "USE") (pin "4") (pinfunction "VSS_4") (pintype "power_in"))
      (node (ref "USE") (pin "EP") (pinfunction "EP_EP") (pintype "passive"))
      (node (ref "USS") (pin "4") (pinfunction "VSS_4") (pintype "power_in"))
      (node (ref "USS") (pin "EP") (pinfunction "EP_EP") (pintype "passive"))
      (node (ref "USW") (pin "4") (pinfunction "VSS_4") (pintype "power_in"))
      (node (ref "USW") (pin "EP") (pinfunction "EP_EP") (pintype "passive"))
      (node (ref "X-NORTH") (pin "102") (pinfunction "102_102") (pintype "bidirectional"))
      (node (ref "X-NORTH") (pin "103") (pinfunction "103_103") (pintype "bidirectional"))
      (node (ref "X-NORTH") (pin "108") (pinfunction "108_108") (pintype "bidirectional"))
      (node (ref "X-NORTH") (pin "114") (pinfunction "114_114") (pintype "bidirectional"))
      (node (ref "X-NORTH") (pin "12") (pinfunction "12_12") (pintype "bidirectional"))
      (node (ref "X-NORTH") (pin "120") (pinfunction "120_120") (pintype "bidirectional"))
      (node (ref "X-NORTH") (pin "126") (pinfunction "126_126") (pintype "bidirectional"))
      (node (ref "X-NORTH") (pin "132") (pinfunction "132_132") (pintype "bidirectional"))
      (node (ref "X-NORTH") (pin "138") (pinfunction "138_138") (pintype "bidirectional"))
      (node (ref "X-NORTH") (pin "139") (pinfunction "139_139") (pintype "bidirectional"))
      (node (ref "X-NORTH") (pin "18") (pinfunction "18_18") (pintype "bidirectional"))
      (node (ref "X-NORTH") (pin "24") (pinfunction "24_24") (pintype "bidirectional"))
      (node (ref "X-NORTH") (pin "30") (pinfunction "30_30") (pintype "bidirectional"))
      (node (ref "X-NORTH") (pin "36") (pinfunction "36_36") (pintype "bidirectional"))
      (node (ref "X-NORTH") (pin "42") (pinfunction "42_42") (pintype "bidirectional"))
      (node (ref "X-NORTH") (pin "43") (pinfunction "43_43") (pintype "bidirectional"))
      (node (ref "X-NORTH") (pin "48") (pinfunction "48_48") (pintype "bidirectional"))
      (node (ref "X-NORTH") (pin "54") (pinfunction "54_54") (pintype "bidirectional"))
      (node (ref "X-NORTH") (pin "60") (pinfunction "60_60") (pintype "bidirectional"))
      (node (ref "X-NORTH") (pin "66") (pinfunction "66_66") (pintype "bidirectional"))
      (node (ref "X-NORTH") (pin "72") (pinfunction "72_72") (pintype "bidirectional"))
      (node (ref "X-NORTH") (pin "78") (pinfunction "78_78") (pintype "bidirectional"))
      (node (ref "X-NORTH") (pin "84") (pinfunction "84_84") (pintype "bidirectional"))
      (node (ref "X-NORTH") (pin "90") (pinfunction "90_90") (pintype "bidirectional"))
      (node (ref "X-NORTH") (pin "96") (pinfunction "96_96") (pintype "bidirectional"))
      (node (ref "X-SOUTH") (pin "102") (pinfunction "102_102") (pintype "bidirectional"))
      (node (ref "X-SOUTH") (pin "103") (pinfunction "103_103") (pintype "bidirectional"))
      (node (ref "X-SOUTH") (pin "108") (pinfunction "108_108") (pintype "bidirectional"))
      (node (ref "X-SOUTH") (pin "114") (pinfunction "114_114") (pintype "bidirectional"))
      (node (ref "X-SOUTH") (pin "12") (pinfunction "12_12") (pintype "bidirectional"))
      (node (ref "X-SOUTH") (pin "120") (pinfunction "120_120") (pintype "bidirectional"))
      (node (ref "X-SOUTH") (pin "126") (pinfunction "126_126") (pintype "bidirectional"))
      (node (ref "X-SOUTH") (pin "132") (pinfunction "132_132") (pintype "bidirectional"))
      (node (ref "X-SOUTH") (pin "138") (pinfunction "138_138") (pintype "bidirectional"))
      (node (ref "X-SOUTH") (pin "139") (pinfunction "139_139") (pintype "bidirectional"))
      (node (ref "X-SOUTH") (pin "18") (pinfunction "18_18") (pintype "bidirectional"))
      (node (ref "X-SOUTH") (pin "24") (pinfunction "24_24") (pintype "bidirectional"))
      (node (ref "X-SOUTH") (pin "30") (pinfunction "30_30") (pintype "bidirectional"))
      (node (ref "X-SOUTH") (pin "36") (pinfunction "36_36") (pintype "bidirectional"))
      (node (ref "X-SOUTH") (pin "42") (pinfunction "42_42") (pintype "bidirectional"))
      (node (ref "X-SOUTH") (pin "43") (pinfunction "43_43") (pintype "bidirectional"))
      (node (ref "X-SOUTH") (pin "48") (pinfunction "48_48") (pintype "bidirectional"))
      (node (ref "X-SOUTH") (pin "54") (pinfunction "54_54") (pintype "bidirectional"))
      (node (ref "X-SOUTH") (pin "60") (pinfunction "60_60") (pintype "bidirectional"))
      (node (ref "X-SOUTH") (pin "66") (pinfunction "66_66") (pintype "bidirectional"))
      (node (ref "X-SOUTH") (pin "72") (pinfunction "72_72") (pintype "bidirectional"))
      (node (ref "X-SOUTH") (pin "78") (pinfunction "78_78") (pintype "bidirectional"))
      (node (ref "X-SOUTH") (pin "84") (pinfunction "84_84") (pintype "bidirectional"))
      (node (ref "X-SOUTH") (pin "90") (pinfunction "90_90") (pintype "bidirectional"))
      (node (ref "X-SOUTH") (pin "96") (pinfunction "96_96") (pintype "bidirectional"))
    )
    (net (code "4") (name "N$38") (class "Default")
      (node (ref "SENSOR") (pin "F4") (pinfunction "DIO1_F4") (pintype "output"))
    )
    (net (code "5") (name "N$39") (class "Default")
      (node (ref "SENSOR") (pin "E4") (pinfunction "DIO2_E4") (pintype "output"))
    )
    (net (code "6") (name "N$40") (class "Default")
      (node (ref "SENSOR") (pin "H4") (pinfunction "DIO3_H4") (pintype "output"))
    )
    (net (code "7") (name "N$41") (class "Default")
      (node (ref "SENSOR") (pin "G3") (pinfunction "DIO4_G3") (pintype "output"))
    )
    (net (code "8") (name "N$42") (class "Default")
      (node (ref "SENSOR") (pin "A2") (pinfunction "TANA_A2") (pintype "output"))
    )
    (net (code "9") (name "N00_N") (class "Default")
      (node (ref "R25") (pin "2") (pinfunction "2_2") (pintype "passive"))
      (node (ref "SENSOR") (pin "E6") (pinfunction "LVDS_CLK_P_E6") (pintype "input"))
      (node (ref "X-NORTH") (pin "16") (pinfunction "16_16") (pintype "bidirectional"))
    )
    (net (code "10") (name "N00_P") (class "Default")
      (node (ref "R25") (pin "1") (pinfunction "1_1") (pintype "passive"))
      (node (ref "SENSOR") (pin "E5") (pinfunction "LVDS_CLK_N_E5") (pintype "input"))
      (node (ref "X-NORTH") (pin "14") (pinfunction "14_14") (pintype "bidirectional"))
    )
    (net (code "11") (name "N01_N") (class "Default")
      (node (ref "SENSOR") (pin "G7") (pinfunction "OUTCLK_P_G7") (pintype "output"))
      (node (ref "X-NORTH") (pin "17") (pinfunction "17_17") (pintype "bidirectional"))
    )
    (net (code "12") (name "N01_P") (class "Default")
      (node (ref "SENSOR") (pin "G6") (pinfunction "OUTCLK_N_G6") (pintype "output"))
      (node (ref "X-NORTH") (pin "15") (pinfunction "15_15") (pintype "bidirectional"))
    )
    (net (code "13") (name "N02_N") (class "Default")
      (node (ref "SENSOR") (pin "F7") (pinfunction "OUT33_P_F7") (pintype "output"))
      (node (ref "X-NORTH") (pin "22") (pinfunction "22_22") (pintype "bidirectional"))
    )
    (net (code "14") (name "N02_P") (class "Default")
      (node (ref "SENSOR") (pin "F6") (pinfunction "OUT33_N_F6") (pintype "output"))
      (node (ref "X-NORTH") (pin "20") (pinfunction "20_20") (pintype "bidirectional"))
    )
    (net (code "15") (name "N03_N") (class "Default")
      (node (ref "X-NORTH") (pin "23") (pinfunction "23_23") (pintype "bidirectional"))
    )
    (net (code "16") (name "N03_P") (class "Default")
      (node (ref "X-NORTH") (pin "21") (pinfunction "21_21") (pintype "bidirectional"))
    )
    (net (code "17") (name "N04_N") (class "Default")
      (node (ref "SENSOR") (pin "E8") (pinfunction "OUT35_P_E8") (pintype "output"))
      (node (ref "X-NORTH") (pin "28") (pinfunction "28_28") (pintype "bidirectional"))
    )
    (net (code "18") (name "N04_P") (class "Default")
      (node (ref "SENSOR") (pin "E7") (pinfunction "OUT35_N_E7") (pintype "output"))
      (node (ref "X-NORTH") (pin "26") (pinfunction "26_26") (pintype "bidirectional"))
    )
    (net (code "19") (name "N05_N") (class "Default")
      (node (ref "SENSOR") (pin "H8") (pinfunction "OUT34_P_H8") (pintype "output"))
      (node (ref "X-NORTH") (pin "29") (pinfunction "29_29") (pintype "bidirectional"))
    )
    (net (code "20") (name "N05_P") (class "Default")
      (node (ref "SENSOR") (pin "H7") (pinfunction "OUT34_N_H7") (pintype "output"))
      (node (ref "X-NORTH") (pin "27") (pinfunction "27_27") (pintype "bidirectional"))
    )
    (net (code "21") (name "N06_N") (class "Default")
      (node (ref "SENSOR") (pin "F9") (pinfunction "OUT37_P_F9") (pintype "output"))
      (node (ref "X-NORTH") (pin "34") (pinfunction "34_34") (pintype "bidirectional"))
    )
    (net (code "22") (name "N06_P") (class "Default")
      (node (ref "SENSOR") (pin "F8") (pinfunction "OUT37_N_F8") (pintype "output"))
      (node (ref "X-NORTH") (pin "32") (pinfunction "32_32") (pintype "bidirectional"))
    )
    (net (code "23") (name "N07_N") (class "Default")
      (node (ref "SENSOR") (pin "G9") (pinfunction "OUT36_P_G9") (pintype "output"))
      (node (ref "X-NORTH") (pin "35") (pinfunction "35_35") (pintype "bidirectional"))
    )
    (net (code "24") (name "N07_P") (class "Default")
      (node (ref "SENSOR") (pin "G8") (pinfunction "OUT36_N_G8") (pintype "output"))
      (node (ref "X-NORTH") (pin "33") (pinfunction "33_33") (pintype "bidirectional"))
    )
    (net (code "25") (name "N08_N") (class "Default")
      (node (ref "SENSOR") (pin "E10") (pinfunction "OUT38_P_E10") (pintype "output"))
      (node (ref "X-NORTH") (pin "40") (pinfunction "40_40") (pintype "bidirectional"))
    )
    (net (code "26") (name "N08_P") (class "Default")
      (node (ref "SENSOR") (pin "E9") (pinfunction "OUT38_N_E9") (pintype "output"))
      (node (ref "X-NORTH") (pin "38") (pinfunction "38_38") (pintype "bidirectional"))
    )
    (net (code "27") (name "N09_N") (class "Default")
      (node (ref "SENSOR") (pin "G11") (pinfunction "OUT39_P_G11") (pintype "output"))
      (node (ref "X-NORTH") (pin "41") (pinfunction "41_41") (pintype "bidirectional"))
    )
    (net (code "28") (name "N09_P") (class "Default")
      (node (ref "SENSOR") (pin "G10") (pinfunction "OUT39_N_G10") (pintype "output"))
      (node (ref "X-NORTH") (pin "39") (pinfunction "39_39") (pintype "bidirectional"))
    )
    (net (code "29") (name "N10_N") (class "Default")
      (node (ref "SENSOR") (pin "F11") (pinfunction "OUT40_P_F11") (pintype "output"))
      (node (ref "X-NORTH") (pin "46") (pinfunction "46_46") (pintype "bidirectional"))
    )
    (net (code "30") (name "N10_P") (class "Default")
      (node (ref "SENSOR") (pin "F10") (pinfunction "OUT40_N_F10") (pintype "output"))
      (node (ref "X-NORTH") (pin "44") (pinfunction "44_44") (pintype "bidirectional"))
    )
    (net (code "31") (name "N11_N") (class "Default")
      (node (ref "SENSOR") (pin "H12") (pinfunction "OUT41_P_H12") (pintype "output"))
      (node (ref "X-NORTH") (pin "47") (pinfunction "47_47") (pintype "bidirectional"))
    )
    (net (code "32") (name "N11_P") (class "Default")
      (node (ref "SENSOR") (pin "H11") (pinfunction "OUT41_N_H11") (pintype "output"))
      (node (ref "X-NORTH") (pin "45") (pinfunction "45_45") (pintype "bidirectional"))
    )
    (net (code "33") (name "N12_N") (class "Default")
      (node (ref "SENSOR") (pin "E12") (pinfunction "OUT42_P_E12") (pintype "output"))
      (node (ref "X-NORTH") (pin "52") (pinfunction "52_52") (pintype "bidirectional"))
    )
    (net (code "34") (name "N12_P") (class "Default")
      (node (ref "SENSOR") (pin "E11") (pinfunction "OUT42_N_E11") (pintype "output"))
      (node (ref "X-NORTH") (pin "50") (pinfunction "50_50") (pintype "bidirectional"))
    )
    (net (code "35") (name "N13_N") (class "Default")
      (node (ref "SENSOR") (pin "G13") (pinfunction "OUT43_P_G13") (pintype "output"))
      (node (ref "X-NORTH") (pin "53") (pinfunction "53_53") (pintype "bidirectional"))
    )
    (net (code "36") (name "N13_P") (class "Default")
      (node (ref "SENSOR") (pin "G12") (pinfunction "OUT43_N_G12") (pintype "output"))
      (node (ref "X-NORTH") (pin "51") (pinfunction "51_51") (pintype "bidirectional"))
    )
    (net (code "37") (name "N14_N") (class "Default")
      (node (ref "SENSOR") (pin "F13") (pinfunction "OUT44_P_F13") (pintype "output"))
      (node (ref "X-NORTH") (pin "58") (pinfunction "58_58") (pintype "bidirectional"))
    )
    (net (code "38") (name "N14_P") (class "Default")
      (node (ref "SENSOR") (pin "F12") (pinfunction "OUT44_N_F12") (pintype "output"))
      (node (ref "X-NORTH") (pin "56") (pinfunction "56_56") (pintype "bidirectional"))
    )
    (net (code "39") (name "N15_N") (class "Default")
      (node (ref "SENSOR") (pin "H14") (pinfunction "OUT45_P_H14") (pintype "output"))
      (node (ref "X-NORTH") (pin "59") (pinfunction "59_59") (pintype "bidirectional"))
    )
    (net (code "40") (name "N15_P") (class "Default")
      (node (ref "SENSOR") (pin "H13") (pinfunction "OUT45_N_H13") (pintype "output"))
      (node (ref "X-NORTH") (pin "57") (pinfunction "57_57") (pintype "bidirectional"))
    )
    (net (code "41") (name "N16_N") (class "Default")
      (node (ref "SENSOR") (pin "E14") (pinfunction "OUT46_P_E14") (pintype "output"))
      (node (ref "X-NORTH") (pin "64") (pinfunction "64_64") (pintype "bidirectional"))
    )
    (net (code "42") (name "N16_P") (class "Default")
      (node (ref "SENSOR") (pin "E13") (pinfunction "OUT46_N_E13") (pintype "output"))
      (node (ref "X-NORTH") (pin "62") (pinfunction "62_62") (pintype "bidirectional"))
    )
    (net (code "43") (name "N17_N") (class "Default")
      (node (ref "SENSOR") (pin "G15") (pinfunction "OUT47_P_G15") (pintype "output"))
      (node (ref "X-NORTH") (pin "65") (pinfunction "65_65") (pintype "bidirectional"))
    )
    (net (code "44") (name "N17_P") (class "Default")
      (node (ref "SENSOR") (pin "G14") (pinfunction "OUT47_N_G14") (pintype "output"))
      (node (ref "X-NORTH") (pin "63") (pinfunction "63_63") (pintype "bidirectional"))
    )
    (net (code "45") (name "N18_N") (class "Default")
      (node (ref "SENSOR") (pin "F15") (pinfunction "OUT48_P_F15") (pintype "output"))
      (node (ref "X-NORTH") (pin "70") (pinfunction "70_70") (pintype "bidirectional"))
    )
    (net (code "46") (name "N18_P") (class "Default")
      (node (ref "SENSOR") (pin "F14") (pinfunction "OUT48_N_F14") (pintype "output"))
      (node (ref "X-NORTH") (pin "68") (pinfunction "68_68") (pintype "bidirectional"))
    )
    (net (code "47") (name "N19_N") (class "Default")
      (node (ref "SENSOR") (pin "G17") (pinfunction "OUT50_P_G17") (pintype "output"))
      (node (ref "X-NORTH") (pin "71") (pinfunction "71_71") (pintype "bidirectional"))
    )
    (net (code "48") (name "N19_P") (class "Default")
      (node (ref "SENSOR") (pin "G16") (pinfunction "OUT50_N_G16") (pintype "output"))
      (node (ref "X-NORTH") (pin "69") (pinfunction "69_69") (pintype "bidirectional"))
    )
    (net (code "49") (name "N20_N") (class "Default")
      (node (ref "SENSOR") (pin "F17") (pinfunction "OUT49_P_F17") (pintype "output"))
      (node (ref "X-NORTH") (pin "76") (pinfunction "76_76") (pintype "bidirectional"))
    )
    (net (code "50") (name "N20_P") (class "Default")
      (node (ref "SENSOR") (pin "F16") (pinfunction "OUT49_N_F16") (pintype "output"))
      (node (ref "X-NORTH") (pin "74") (pinfunction "74_74") (pintype "bidirectional"))
    )
    (net (code "51") (name "N21_N") (class "Default")
      (node (ref "SENSOR") (pin "H18") (pinfunction "OUT52_P_H18") (pintype "output"))
      (node (ref "X-NORTH") (pin "77") (pinfunction "77_77") (pintype "bidirectional"))
    )
    (net (code "52") (name "N21_P") (class "Default")
      (node (ref "SENSOR") (pin "H17") (pinfunction "OUT52_N_H17") (pintype "output"))
      (node (ref "X-NORTH") (pin "75") (pinfunction "75_75") (pintype "bidirectional"))
    )
    (net (code "53") (name "N22_N") (class "Default")
      (node (ref "SENSOR") (pin "E18") (pinfunction "OUT51_P_E18") (pintype "output"))
      (node (ref "X-NORTH") (pin "82") (pinfunction "82_82") (pintype "bidirectional"))
    )
    (net (code "54") (name "N22_P") (class "Default")
      (node (ref "SENSOR") (pin "E17") (pinfunction "OUT51_N_E17") (pintype "output"))
      (node (ref "X-NORTH") (pin "80") (pinfunction "80_80") (pintype "bidirectional"))
    )
    (net (code "55") (name "N23_N") (class "Default")
      (node (ref "SENSOR") (pin "G19") (pinfunction "OUT54_P_G19") (pintype "output"))
      (node (ref "X-NORTH") (pin "83") (pinfunction "83_83") (pintype "bidirectional"))
    )
    (net (code "56") (name "N23_P") (class "Default")
      (node (ref "SENSOR") (pin "G18") (pinfunction "OUT54_N_G18") (pintype "output"))
      (node (ref "X-NORTH") (pin "81") (pinfunction "81_81") (pintype "bidirectional"))
    )
    (net (code "57") (name "N24_N") (class "Default")
      (node (ref "SENSOR") (pin "F19") (pinfunction "OUT53_P_F19") (pintype "output"))
      (node (ref "X-NORTH") (pin "88") (pinfunction "88_88") (pintype "bidirectional"))
    )
    (net (code "58") (name "N24_P") (class "Default")
      (node (ref "SENSOR") (pin "F18") (pinfunction "OUT53_N_F18") (pintype "output"))
      (node (ref "X-NORTH") (pin "86") (pinfunction "86_86") (pintype "bidirectional"))
    )
    (net (code "59") (name "N25_N") (class "Default")
      (node (ref "SENSOR") (pin "H20") (pinfunction "OUT56_P_H20") (pintype "output"))
      (node (ref "X-NORTH") (pin "89") (pinfunction "89_89") (pintype "bidirectional"))
    )
    (net (code "60") (name "N25_P") (class "Default")
      (node (ref "SENSOR") (pin "H19") (pinfunction "OUT56_N_H19") (pintype "output"))
      (node (ref "X-NORTH") (pin "87") (pinfunction "87_87") (pintype "bidirectional"))
    )
    (net (code "61") (name "N26_N") (class "Default")
      (node (ref "SENSOR") (pin "E20") (pinfunction "OUT55_P_E20") (pintype "output"))
      (node (ref "X-NORTH") (pin "94") (pinfunction "94_94") (pintype "bidirectional"))
    )
    (net (code "62") (name "N26_P") (class "Default")
      (node (ref "SENSOR") (pin "E19") (pinfunction "OUT55_N_E19") (pintype "output"))
      (node (ref "X-NORTH") (pin "92") (pinfunction "92_92") (pintype "bidirectional"))
    )
    (net (code "63") (name "N27_N") (class "Default")
      (node (ref "SENSOR") (pin "G21") (pinfunction "OUT58_P_G21") (pintype "output"))
      (node (ref "X-NORTH") (pin "95") (pinfunction "95_95") (pintype "bidirectional"))
    )
    (net (code "64") (name "N27_P") (class "Default")
      (node (ref "SENSOR") (pin "G20") (pinfunction "OUT58_N_G20") (pintype "output"))
      (node (ref "X-NORTH") (pin "93") (pinfunction "93_93") (pintype "bidirectional"))
    )
    (net (code "65") (name "N28_N") (class "Default")
      (node (ref "SENSOR") (pin "F21") (pinfunction "OUT57_P_F21") (pintype "output"))
      (node (ref "X-NORTH") (pin "100") (pinfunction "100_100") (pintype "bidirectional"))
    )
    (net (code "66") (name "N28_P") (class "Default")
      (node (ref "SENSOR") (pin "F20") (pinfunction "OUT57_N_F20") (pintype "output"))
      (node (ref "X-NORTH") (pin "98") (pinfunction "98_98") (pintype "bidirectional"))
    )
    (net (code "67") (name "N29_N") (class "Default")
      (node (ref "SENSOR") (pin "G23") (pinfunction "OUT61_P_G23") (pintype "output"))
      (node (ref "X-NORTH") (pin "101") (pinfunction "101_101") (pintype "bidirectional"))
    )
    (net (code "68") (name "N29_P") (class "Default")
      (node (ref "SENSOR") (pin "G22") (pinfunction "OUT61_N_G22") (pintype "output"))
      (node (ref "X-NORTH") (pin "99") (pinfunction "99_99") (pintype "bidirectional"))
    )
    (net (code "69") (name "N30_N") (class "Default")
      (node (ref "SENSOR") (pin "E22") (pinfunction "OUT59_P_E22") (pintype "output"))
      (node (ref "X-NORTH") (pin "106") (pinfunction "106_106") (pintype "bidirectional"))
    )
    (net (code "70") (name "N30_P") (class "Default")
      (node (ref "SENSOR") (pin "E21") (pinfunction "OUT59_N_E21") (pintype "output"))
      (node (ref "X-NORTH") (pin "104") (pinfunction "104_104") (pintype "bidirectional"))
    )
    (net (code "71") (name "N31_N") (class "Default")
      (node (ref "SENSOR") (pin "H24") (pinfunction "OUT63_P_H24") (pintype "output"))
      (node (ref "X-NORTH") (pin "107") (pinfunction "107_107") (pintype "bidirectional"))
    )
    (net (code "72") (name "N31_P") (class "Default")
      (node (ref "SENSOR") (pin "H23") (pinfunction "OUT63_N_H23") (pintype "output"))
      (node (ref "X-NORTH") (pin "105") (pinfunction "105_105") (pintype "bidirectional"))
    )
    (net (code "73") (name "N32_N") (class "Default")
      (node (ref "SENSOR") (pin "F23") (pinfunction "OUT60_P_F23") (pintype "output"))
      (node (ref "X-NORTH") (pin "112") (pinfunction "112_112") (pintype "bidirectional"))
    )
    (net (code "74") (name "N32_P") (class "Default")
      (node (ref "SENSOR") (pin "F22") (pinfunction "OUT60_N_F22") (pintype "output"))
      (node (ref "X-NORTH") (pin "110") (pinfunction "110_110") (pintype "bidirectional"))
    )
    (net (code "75") (name "N33_N") (class "Default")
      (node (ref "SENSOR") (pin "G25") (pinfunction "OUT64_P_G25") (pintype "output"))
      (node (ref "X-NORTH") (pin "113") (pinfunction "113_113") (pintype "bidirectional"))
    )
    (net (code "76") (name "N33_P") (class "Default")
      (node (ref "SENSOR") (pin "G24") (pinfunction "OUT64_N_G24") (pintype "output"))
      (node (ref "X-NORTH") (pin "111") (pinfunction "111_111") (pintype "bidirectional"))
    )
    (net (code "77") (name "N34_N") (class "Default")
      (node (ref "SENSOR") (pin "E24") (pinfunction "OUT62_P_E24") (pintype "output"))
      (node (ref "X-NORTH") (pin "118") (pinfunction "118_118") (pintype "bidirectional"))
    )
    (net (code "78") (name "N34_P") (class "Default")
      (node (ref "SENSOR") (pin "E23") (pinfunction "OUT62_N_E23") (pintype "output"))
      (node (ref "X-NORTH") (pin "116") (pinfunction "116_116") (pintype "bidirectional"))
    )
    (net (code "79") (name "N35_N") (class "Default")
      (node (ref "U6") (pin "4") (pinfunction "A4_4") (pintype "bidirectional"))
      (node (ref "X-NORTH") (pin "119") (pinfunction "119_119") (pintype "bidirectional"))
    )
    (net (code "80") (name "N35_P") (class "Default")
      (node (ref "U6") (pin "3") (pinfunction "A3_3") (pintype "bidirectional"))
      (node (ref "X-NORTH") (pin "117") (pinfunction "117_117") (pintype "bidirectional"))
    )
    (net (code "81") (name "N36_N") (class "Default")
      (node (ref "X-NORTH") (pin "124") (pinfunction "124_124") (pintype "bidirectional"))
    )
    (net (code "82") (name "N36_P") (class "Default")
      (node (ref "X-NORTH") (pin "122") (pinfunction "122_122") (pintype "bidirectional"))
    )
    (net (code "83") (name "N37_N") (class "Default")
      (node (ref "U5") (pin "3") (pinfunction "A3_3") (pintype "bidirectional"))
      (node (ref "X-NORTH") (pin "125") (pinfunction "125_125") (pintype "bidirectional"))
    )
    (net (code "84") (name "N37_P") (class "Default")
      (node (ref "U5") (pin "4") (pinfunction "A4_4") (pintype "bidirectional"))
      (node (ref "X-NORTH") (pin "123") (pinfunction "123_123") (pintype "bidirectional"))
    )
    (net (code "85") (name "N38_N") (class "Default")
      (node (ref "U6") (pin "2") (pinfunction "A2_2") (pintype "bidirectional"))
      (node (ref "X-NORTH") (pin "130") (pinfunction "130_130") (pintype "bidirectional"))
    )
    (net (code "86") (name "N38_P") (class "Default")
      (node (ref "U6") (pin "1") (pinfunction "A1_1") (pintype "bidirectional"))
      (node (ref "X-NORTH") (pin "128") (pinfunction "128_128") (pintype "bidirectional"))
    )
    (net (code "87") (name "N39_N") (class "Default")
      (node (ref "U5") (pin "1") (pinfunction "A1_1") (pintype "bidirectional"))
      (node (ref "X-NORTH") (pin "131") (pinfunction "131_131") (pintype "bidirectional"))
    )
    (net (code "88") (name "N39_P") (class "Default")
      (node (ref "U5") (pin "2") (pinfunction "A2_2") (pintype "bidirectional"))
      (node (ref "X-NORTH") (pin "129") (pinfunction "129_129") (pintype "bidirectional"))
    )
    (net (code "89") (name "N_CHK_V") (class "Default")
      (node (ref "C2") (pin "1") (pinfunction "1_1") (pintype "passive"))
      (node (ref "C3") (pin "1") (pinfunction "1_1") (pintype "passive"))
      (node (ref "C4") (pin "1") (pinfunction "1_1") (pintype "passive"))
      (node (ref "R19") (pin "1") (pinfunction "1_1") (pintype "passive"))
      (node (ref "TP1") (pin "TP") (pinfunction "TP_TP") (pintype "input"))
      (node (ref "UNE") (pin "8") (pinfunction "VDD_8") (pintype "power_in"))
      (node (ref "UNN") (pin "8") (pinfunction "VDD_8") (pintype "power_in"))
      (node (ref "UNW") (pin "8") (pinfunction "VDD_8") (pintype "power_in"))
      (node (ref "X-NORTH") (pin "10") (pinfunction "10_10") (pintype "bidirectional"))
      (node (ref "X-NORTH") (pin "8") (pinfunction "8_8") (pintype "bidirectional"))
    )
    (net (code "90") (name "N_I2C_V") (class "Default")
      (node (ref "C1") (pin "1") (pinfunction "1_1") (pintype "passive"))
      (node (ref "R1X") (pin "1") (pinfunction "1_1") (pintype "passive"))
      (node (ref "UEP") (pin "8") (pinfunction "VCC_8") (pintype "power_in"))
      (node (ref "X-NORTH") (pin "135") (pinfunction "135_135") (pintype "bidirectional"))
      (node (ref "X-NORTH") (pin "137") (pinfunction "137_137") (pintype "bidirectional"))
    )
    (net (code "91") (name "N_REF") (class "Default")
      (node (ref "R19") (pin "2") (pinfunction "2_2") (pintype "passive"))
      (node (ref "TP2") (pin "TP") (pinfunction "TP_TP") (pintype "input"))
      (node (ref "U1") (pin "3") (pinfunction "CATHODE_3") (pintype "output"))
      (node (ref "U1") (pin "4") (pinfunction "REF_4") (pintype "input"))
      (node (ref "UNE") (pin "2") (pinfunction "VINA-_2") (pintype "input"))
      (node (ref "UNE") (pin "5") (pinfunction "VINB+_5") (pintype "input"))
      (node (ref "UNN") (pin "2") (pinfunction "VINA-_2") (pintype "input"))
      (node (ref "UNN") (pin "5") (pinfunction "VINB+_5") (pintype "input"))
      (node (ref "UNW") (pin "2") (pinfunction "VINA-_2") (pintype "input"))
      (node (ref "UNW") (pin "5") (pinfunction "VINB+_5") (pintype "input"))
    )
    (net (code "92") (name "N_SCK") (class "Default")
      (node (ref "U4") (pin "15") (pinfunction "1B1_15") (pintype "output"))
      (node (ref "X-NORTH") (pin "144") (pinfunction "144_144") (pintype "bidirectional"))
    )
    (net (code "93") (name "N_SCL") (class "Default")
      (node (ref "UEP") (pin "6") (pinfunction "SCL_6") (pintype "input"))
      (node (ref "X-NORTH") (pin "143") (pinfunction "143_143") (pintype "bidirectional"))
    )
    (net (code "94") (name "N_SDA") (class "Default")
      (node (ref "UEP") (pin "5") (pinfunction "SDA_5") (pintype "bidirectional"))
      (node (ref "X-NORTH") (pin "141") (pinfunction "141_141") (pintype "bidirectional"))
    )
    (net (code "95") (name "N_SDI") (class "Default")
      (node (ref "U4") (pin "13") (pinfunction "2B1_13") (pintype "output"))
      (node (ref "X-NORTH") (pin "140") (pinfunction "140_140") (pintype "bidirectional"))
    )
    (net (code "96") (name "N_SDO") (class "Default")
      (node (ref "U4") (pin "14") (pinfunction "1B2_14") (pintype "output"))
      (node (ref "X-NORTH") (pin "142") (pinfunction "142_142") (pintype "bidirectional"))
    )
    (net (code "97") (name "N_SPI_V") (class "Default")
      (node (ref "C71") (pin "1") (pinfunction "1_1") (pintype "passive"))
      (node (ref "U4") (pin "2") (pinfunction "VCCB_2") (pintype "power_in"))
      (node (ref "X-NORTH") (pin "134") (pinfunction "134_134") (pintype "bidirectional"))
      (node (ref "X-NORTH") (pin "136") (pinfunction "136_136") (pintype "bidirectional"))
    )
    (net (code "98") (name "N_VE") (class "Default")
      (node (ref "C50") (pin "1") (pinfunction "1_1") (pintype "passive"))
      (node (ref "C51") (pin "1") (pinfunction "1_1") (pintype "passive"))
      (node (ref "C52") (pin "1") (pinfunction "1_1") (pintype "passive"))
      (node (ref "C53") (pin "1") (pinfunction "1_1") (pintype "passive"))
      (node (ref "C54") (pin "1") (pinfunction "1_1") (pintype "passive"))
      (node (ref "C55") (pin "1") (pinfunction "1_1") (pintype "passive"))
      (node (ref "C56") (pin "1") (pinfunction "1_1") (pintype "passive"))
      (node (ref "C67") (pin "1") (pinfunction "1_1") (pintype "passive"))
      (node (ref "C69") (pin "1") (pinfunction "1_1") (pintype "passive"))
      (node (ref "C75") (pin "1") (pinfunction "1_1") (pintype "passive"))
      (node (ref "C76") (pin "1") (pinfunction "1_1") (pintype "passive"))
      (node (ref "C77") (pin "1") (pinfunction "1_1") (pintype "passive"))
      (node (ref "C84") (pin "1") (pinfunction "1_1") (pintype "passive"))
      (node (ref "C85") (pin "1") (pinfunction "1_1") (pintype "passive"))
      (node (ref "C86") (pin "1") (pinfunction "1_1") (pintype "passive"))
      (node (ref "SENSOR") (pin "C26") (pinfunction "VDD33_C26") (pintype "power_in"))
      (node (ref "SENSOR") (pin "C27") (pinfunction "VDD33_C27") (pintype "power_in"))
      (node (ref "SENSOR") (pin "D26") (pinfunction "VDD33_D26") (pintype "power_in"))
      (node (ref "SENSOR") (pin "D3") (pinfunction "VDD33_D3") (pintype "power_in"))
      (node (ref "SENSOR") (pin "E26") (pinfunction "VDD33_E26") (pintype "power_in"))
      (node (ref "SENSOR") (pin "F26") (pinfunction "VDD33_F26") (pintype "power_in"))
      (node (ref "SENSOR") (pin "F5") (pinfunction "VDD33_F5") (pintype "power_in"))
      (node (ref "TP7") (pin "TP") (pinfunction "TP_TP") (pintype "input"))
      (node (ref "U4") (pin "3") (pinfunction "VCCA_3") (pintype "power_in"))
      (node (ref "U4") (pin "5") (pinfunction "2DIR_5") (pintype "input"))
      (node (ref "U5") (pin "13") (pinfunction "VCCB_13") (pintype "power_in"))
      (node (ref "U6") (pin "13") (pinfunction "VCCB_13") (pintype "power_in"))
      (node (ref "X-NORTH") (pin "109") (pinfunction "109_109") (pintype "bidirectional"))
      (node (ref "X-NORTH") (pin "115") (pinfunction "115_115") (pintype "bidirectional"))
      (node (ref "X-NORTH") (pin "121") (pinfunction "121_121") (pintype "bidirectional"))
      (node (ref "X-NORTH") (pin "127") (pinfunction "127_127") (pintype "bidirectional"))
      (node (ref "X-NORTH") (pin "133") (pinfunction "133_133") (pintype "bidirectional"))
    )
    (net (code "99") (name "N_VE_CV") (class "Default")
      (node (ref "C10") (pin "1") (pinfunction "1_1") (pintype "passive"))
      (node (ref "R7") (pin "1") (pinfunction "1_1") (pintype "passive"))
      (node (ref "X-NORTH") (pin "6") (pinfunction "6_6") (pintype "bidirectional"))
    )
    (net (code "100") (name "N_VE_OV") (class "Default")
      (node (ref "UNE") (pin "7") (pinfunction "OUTB_7") (pintype "output"))
      (node (ref "X-NORTH") (pin "5") (pinfunction "5_5") (pintype "bidirectional"))
    )
    (net (code "101") (name "N_VE_UV") (class "Default")
      (node (ref "UNE") (pin "1") (pinfunction "OUTA_1") (pintype "output"))
      (node (ref "X-NORTH") (pin "11") (pinfunction "11_11") (pintype "bidirectional"))
    )
    (net (code "102") (name "N_VN") (class "Default")
      (node (ref "C31") (pin "1") (pinfunction "1_1") (pintype "passive"))
      (node (ref "C32") (pin "1") (pinfunction "1_1") (pintype "passive"))
      (node (ref "C33") (pin "1") (pinfunction "1_1") (pintype "passive"))
      (node (ref "C34") (pin "1") (pinfunction "1_1") (pintype "passive"))
      (node (ref "C35") (pin "1") (pinfunction "1_1") (pintype "passive"))
      (node (ref "C36") (pin "1") (pinfunction "1_1") (pintype "passive"))
      (node (ref "C37") (pin "1") (pinfunction "1_1") (pintype "passive"))
      (node (ref "C38") (pin "1") (pinfunction "1_1") (pintype "passive"))
      (node (ref "C39") (pin "1") (pinfunction "1_1") (pintype "passive"))
      (node (ref "C40") (pin "1") (pinfunction "1_1") (pintype "passive"))
      (node (ref "C41") (pin "1") (pinfunction "1_1") (pintype "passive"))
      (node (ref "C42") (pin "1") (pinfunction "1_1") (pintype "passive"))
      (node (ref "C43") (pin "1") (pinfunction "1_1") (pintype "passive"))
      (node (ref "C44") (pin "1") (pinfunction "1_1") (pintype "passive"))
      (node (ref "C68") (pin "1") (pinfunction "1_1") (pintype "passive"))
      (node (ref "C70") (pin "1") (pinfunction "1_1") (pintype "passive"))
      (node (ref "C78") (pin "1") (pinfunction "1_1") (pintype "passive"))
      (node (ref "C79") (pin "1") (pinfunction "1_1") (pintype "passive"))
      (node (ref "C80") (pin "1") (pinfunction "1_1") (pintype "passive"))
      (node (ref "C87") (pin "1") (pinfunction "1_1") (pintype "passive"))
      (node (ref "C88") (pin "1") (pinfunction "1_1") (pintype "passive"))
      (node (ref "C89") (pin "1") (pinfunction "1_1") (pintype "passive"))
      (node (ref "SENSOR") (pin "A10") (pinfunction "VDD18_A10") (pintype "power_in"))
      (node (ref "SENSOR") (pin "A15") (pinfunction "VDD18_A15") (pintype "power_in"))
      (node (ref "SENSOR") (pin "A16") (pinfunction "VDD18_A16") (pintype "power_in"))
      (node (ref "SENSOR") (pin "A22") (pinfunction "VDD18_A22") (pintype "power_in"))
      (node (ref "SENSOR") (pin "A26") (pinfunction "VDD18_A26") (pintype "power_in"))
      (node (ref "SENSOR") (pin "A27") (pinfunction "VDD18_A27") (pintype "power_in"))
      (node (ref "SENSOR") (pin "B4") (pinfunction "VDD18_B4") (pintype "power_in"))
      (node (ref "SENSOR") (pin "E1") (pinfunction "VDD18_PLL_E1") (pintype "power_in"))
      (node (ref "SENSOR") (pin "H10") (pinfunction "VDD18_H10") (pintype "power_in"))
      (node (ref "SENSOR") (pin "H15") (pinfunction "VDD18_H15") (pintype "power_in"))
      (node (ref "SENSOR") (pin "H16") (pinfunction "VDD18_H16") (pintype "power_in"))
      (node (ref "SENSOR") (pin "H22") (pinfunction "VDD18_H22") (pintype "power_in"))
      (node (ref "SENSOR") (pin "H26") (pinfunction "VDD18_H26") (pintype "power_in"))
      (node (ref "SENSOR") (pin "H5") (pinfunction "VDD18_H5") (pintype "power_in"))
      (node (ref "TP5") (pin "TP") (pinfunction "TP_TP") (pintype "input"))
      (node (ref "U5") (pin "14") (pinfunction "VCCA_14") (pintype "power_in"))
      (node (ref "U5") (pin "15") (pinfunction "DIR1_15") (pintype "input"))
      (node (ref "U5") (pin "16") (pinfunction "DIR2_16") (pintype "input"))
      (node (ref "U5") (pin "5") (pinfunction "DIR3_5") (pintype "input"))
      (node (ref "U6") (pin "14") (pinfunction "VCCA_14") (pintype "power_in"))
      (node (ref "U6") (pin "16") (pinfunction "DIR2_16") (pintype "input"))
      (node (ref "X-NORTH") (pin "49") (pinfunction "49_49") (pintype "bidirectional"))
      (node (ref "X-NORTH") (pin "55") (pinfunction "55_55") (pintype "bidirectional"))
      (node (ref "X-NORTH") (pin "61") (pinfunction "61_61") (pintype "bidirectional"))
      (node (ref "X-NORTH") (pin "67") (pinfunction "67_67") (pintype "bidirectional"))
      (node (ref "X-NORTH") (pin "73") (pinfunction "73_73") (pintype "bidirectional"))
      (node (ref "X-NORTH") (pin "79") (pinfunction "79_79") (pintype "bidirectional"))
      (node (ref "X-NORTH") (pin "85") (pinfunction "85_85") (pintype "bidirectional"))
      (node (ref "X-NORTH") (pin "91") (pinfunction "91_91") (pintype "bidirectional"))
      (node (ref "X-NORTH") (pin "97") (pinfunction "97_97") (pintype "bidirectional"))
    )
    (net (code "103") (name "N_VN_CV") (class "Default")
      (node (ref "C9") (pin "1") (pinfunction "1_1") (pintype "passive"))
      (node (ref "R4") (pin "1") (pinfunction "1_1") (pintype "passive"))
      (node (ref "X-NORTH") (pin "4") (pinfunction "4_4") (pintype "bidirectional"))
    )
    (net (code "104") (name "N_VN_OV") (class "Default")
      (node (ref "UNN") (pin "7") (pinfunction "OUTB_7") (pintype "output"))
      (node (ref "X-NORTH") (pin "3") (pinfunction "3_3") (pintype "bidirectional"))
    )
    (net (code "105") (name "N_VN_UV") (class "Default")
      (node (ref "UNN") (pin "1") (pinfunction "OUTA_1") (pintype "output"))
      (node (ref "X-NORTH") (pin "9") (pinfunction "9_9") (pintype "bidirectional"))
    )
    (net (code "106") (name "N_VW") (class "Default")
      (node (ref "C57") (pin "1") (pinfunction "1_1") (pintype "passive"))
      (node (ref "C58") (pin "1") (pinfunction "1_1") (pintype "passive"))
      (node (ref "C59") (pin "1") (pinfunction "1_1") (pintype "passive"))
      (node (ref "SENSOR") (pin "E2") (pinfunction "VDD_RES_E2") (pintype "power_in"))
      (node (ref "SENSOR") (pin "G4") (pinfunction "VDD_RES_G4") (pintype "power_in"))
      (node (ref "TP8") (pin "TP") (pinfunction "TP_TP") (pintype "input"))
      (node (ref "X-NORTH") (pin "13") (pinfunction "13_13") (pintype "bidirectional"))
      (node (ref "X-NORTH") (pin "19") (pinfunction "19_19") (pintype "bidirectional"))
      (node (ref "X-NORTH") (pin "25") (pinfunction "25_25") (pintype "bidirectional"))
      (node (ref "X-NORTH") (pin "31") (pinfunction "31_31") (pintype "bidirectional"))
      (node (ref "X-NORTH") (pin "37") (pinfunction "37_37") (pintype "bidirectional"))
    )
    (net (code "107") (name "N_VW_CV") (class "Default")
      (node (ref "C8") (pin "1") (pinfunction "1_1") (pintype "passive"))
      (node (ref "R1") (pin "1") (pinfunction "1_1") (pintype "passive"))
      (node (ref "X-NORTH") (pin "2") (pinfunction "2_2") (pintype "bidirectional"))
    )
    (net (code "108") (name "N_VW_OV") (class "Default")
      (node (ref "UNW") (pin "7") (pinfunction "OUTB_7") (pintype "output"))
      (node (ref "X-NORTH") (pin "1") (pinfunction "1_1") (pintype "bidirectional"))
    )
    (net (code "109") (name "N_VW_UV") (class "Default")
      (node (ref "UNW") (pin "1") (pinfunction "OUTA_1") (pintype "output"))
      (node (ref "X-NORTH") (pin "7") (pinfunction "7_7") (pintype "bidirectional"))
    )
    (net (code "110") (name "Net-(SENSORB-CMDN)") (class "Default")
      (node (ref "C61") (pin "1") (pinfunction "1_1") (pintype "passive"))
      (node (ref "SENSOR") (pin "F1") (pinfunction "CMDN_F1") (pintype "bidirectional"))
    )
    (net (code "111") (name "Net-(SENSORB-CMDP)") (class "Default")
      (node (ref "C22") (pin "2") (pinfunction "2_2") (pintype "passive"))
      (node (ref "SENSOR") (pin "F2") (pinfunction "CMDP_F2") (pintype "bidirectional"))
    )
    (net (code "112") (name "Net-(SENSORB-CMDP_COMP)") (class "Default")
      (node (ref "C28") (pin "2") (pinfunction "2_2") (pintype "passive"))
      (node (ref "SENSOR") (pin "H3") (pinfunction "CMDP_COMP_H3") (pintype "bidirectional"))
    )
    (net (code "113") (name "Net-(SENSORB-CMDP_COMP_INV)") (class "Default")
      (node (ref "C27") (pin "2") (pinfunction "2_2") (pintype "passive"))
      (node (ref "SENSOR") (pin "F3") (pinfunction "CMDP_COMP_INV_F3") (pintype "bidirectional"))
    )
    (net (code "114") (name "Net-(SENSORB-CMD_COLAMP)") (class "Default")
      (node (ref "C25") (pin "2") (pinfunction "2_2") (pintype "passive"))
      (node (ref "SENSOR") (pin "C6") (pinfunction "CMD_COLAMP_C6") (pintype "bidirectional"))
    )
    (net (code "115") (name "Net-(SENSORB-CMD_COL_LOAD)") (class "Default")
      (node (ref "C23") (pin "2") (pinfunction "2_2") (pintype "passive"))
      (node (ref "SENSOR") (pin "B1") (pinfunction "CMD_COL_LOAD_B1") (pintype "bidirectional"))
    )
    (net (code "116") (name "Net-(SENSORB-CMD_COL_PC)") (class "Default")
      (node (ref "C26") (pin "2") (pinfunction "2_2") (pintype "passive"))
      (node (ref "SENSOR") (pin "D1") (pinfunction "CMD_COL_PC_D1") (pintype "bidirectional"))
    )
    (net (code "117") (name "Net-(SENSORB-CMD_LVDS)") (class "Default")
      (node (ref "C62") (pin "1") (pinfunction "1_1") (pintype "passive"))
      (node (ref "SENSOR") (pin "C1") (pinfunction "CMD_LVDS_C1") (pintype "bidirectional"))
    )
    (net (code "118") (name "Net-(SENSORB-CMD_RAMP)") (class "Default")
      (node (ref "C24") (pin "2") (pinfunction "2_2") (pintype "passive"))
      (node (ref "SENSOR") (pin "B29") (pinfunction "CMD_RAMP_B29") (pintype "bidirectional"))
    )
    (net (code "119") (name "Net-(SENSORB-VBGAP)") (class "Default")
      (node (ref "C64") (pin "1") (pinfunction "1_1") (pintype "passive"))
      (node (ref "SENSOR") (pin "C29") (pinfunction "VBGAP_C29") (pintype "bidirectional"))
    )
    (net (code "120") (name "Net-(SENSORB-VCLAMP)") (class "Default")
      (node (ref "C63") (pin "1") (pinfunction "1_1") (pintype "passive"))
      (node (ref "SENSOR") (pin "D4") (pinfunction "VCLAMP_D4") (pintype "bidirectional"))
    )
    (net (code "121") (name "Net-(SENSORB-VCLAMP_ADC)") (class "Default")
      (node (ref "C60") (pin "1") (pinfunction "1_1") (pintype "passive"))
      (node (ref "SENSOR") (pin "G2") (pinfunction "VCLAMP_ADC_G2") (pintype "bidirectional"))
    )
    (net (code "122") (name "Net-(SENSORB-VPCH_H)") (class "Default")
      (node (ref "C92") (pin "1") (pinfunction "1_1") (pintype "passive"))
      (node (ref "SENSOR") (pin "C4") (pinfunction "VPCH_H_C4") (pintype "bidirectional"))
    )
    (net (code "123") (name "Net-(SENSORB-VPCH_L)") (class "Default")
      (node (ref "C14") (pin "1") (pinfunction "1_1") (pintype "passive"))
      (node (ref "SENSOR") (pin "A4") (pinfunction "VPCH_L_A4") (pintype "bidirectional"))
    )
    (net (code "124") (name "Net-(SENSORB-VREF)") (class "Default")
      (node (ref "C29") (pin "1") (pinfunction "1_1") (pintype "passive"))
      (node (ref "SENSOR") (pin "A3") (pinfunction "VREF_A3") (pintype "bidirectional"))
    )
    (net (code "125") (name "Net-(SENSORB-VREF_ADC)") (class "Default")
      (node (ref "C30") (pin "1") (pinfunction "1_1") (pintype "passive"))
      (node (ref "SENSOR") (pin "B3") (pinfunction "VREF_ADC_B3") (pintype "bidirectional"))
    )
    (net (code "126") (name "Net-(SENSORB-VRES_L)") (class "Default")
      (node (ref "C15") (pin "1") (pinfunction "1_1") (pintype "passive"))
      (node (ref "SENSOR") (pin "D5") (pinfunction "VRES_L_D5") (pintype "bidirectional"))
    )
    (net (code "127") (name "Net-(SENSORB-VTF_LOW0)") (class "Default")
      (node (ref "C18") (pin "1") (pinfunction "1_1") (pintype "passive"))
      (node (ref "SENSOR") (pin "C5") (pinfunction "VTF_LOW0_C5") (pintype "bidirectional"))
    )
    (net (code "128") (name "Net-(SENSORB-VTF_LOW1)") (class "Default")
      (node (ref "C19") (pin "1") (pinfunction "1_1") (pintype "passive"))
      (node (ref "SENSOR") (pin "D6") (pinfunction "VTF_LOW1_D6") (pintype "bidirectional"))
    )
    (net (code "129") (name "Net-(SENSORB-VTF_LOW2)") (class "Default")
      (node (ref "C20") (pin "1") (pinfunction "1_1") (pintype "passive"))
      (node (ref "SENSOR") (pin "B30") (pinfunction "VTF_LOW2_B30") (pintype "bidirectional"))
    )
    (net (code "130") (name "Net-(SENSORB-VTF_LOW3)") (class "Default")
      (node (ref "C21") (pin "1") (pinfunction "1_1") (pintype "passive"))
      (node (ref "SENSOR") (pin "C30") (pinfunction "VTF_LOW3_C30") (pintype "bidirectional"))
    )
    (net (code "131") (name "Net-(U3-ADJ)") (class "Default")
      (node (ref "R21") (pin "1") (pinfunction "1_1") (pintype "passive"))
      (node (ref "R22") (pin "2") (pinfunction "2_2") (pintype "passive"))
      (node (ref "U3") (pin "5") (pinfunction "ADJ_5") (pintype "input"))
    )
    (net (code "132") (name "Net-(UEP-WP)") (class "Default")
      (node (ref "R1X") (pin "2") (pinfunction "2_2") (pintype "passive"))
      (node (ref "R2X") (pin "1") (pinfunction "1_1") (pintype "passive"))
      (node (ref "UEP") (pin "7") (pinfunction "WP_7") (pintype "input"))
    )
    (net (code "133") (name "Net-(UNE-VINA+)") (class "Default")
      (node (ref "R7") (pin "2") (pinfunction "2_2") (pintype "passive"))
      (node (ref "R8") (pin "1") (pinfunction "1_1") (pintype "passive"))
      (node (ref "UNE") (pin "3") (pinfunction "VINA+_3") (pintype "input"))
    )
    (net (code "134") (name "Net-(UNE-VINB-)") (class "Default")
      (node (ref "R8") (pin "2") (pinfunction "2_2") (pintype "passive"))
      (node (ref "R9") (pin "1") (pinfunction "1_1") (pintype "passive"))
      (node (ref "UNE") (pin "6") (pinfunction "VINB-_6") (pintype "input"))
    )
    (net (code "135") (name "Net-(UNN-VINA+)") (class "Default")
      (node (ref "R4") (pin "2") (pinfunction "2_2") (pintype "passive"))
      (node (ref "R5") (pin "1") (pinfunction "1_1") (pintype "passive"))
      (node (ref "UNN") (pin "3") (pinfunction "VINA+_3") (pintype "input"))
    )
    (net (code "136") (name "Net-(UNN-VINB-)") (class "Default")
      (node (ref "R5") (pin "2") (pinfunction "2_2") (pintype "passive"))
      (node (ref "R6") (pin "1") (pinfunction "1_1") (pintype "passive"))
      (node (ref "UNN") (pin "6") (pinfunction "VINB-_6") (pintype "input"))
    )
    (net (code "137") (name "Net-(UNW-VINA+)") (class "Default")
      (node (ref "R1") (pin "2") (pinfunction "2_2") (pintype "passive"))
      (node (ref "R2") (pin "1") (pinfunction "1_1") (pintype "passive"))
      (node (ref "UNW") (pin "3") (pinfunction "VINA+_3") (pintype "input"))
    )
    (net (code "138") (name "Net-(UNW-VINB-)") (class "Default")
      (node (ref "R2") (pin "2") (pinfunction "2_2") (pintype "passive"))
      (node (ref "R3") (pin "1") (pinfunction "1_1") (pintype "passive"))
      (node (ref "UNW") (pin "6") (pinfunction "VINB-_6") (pintype "input"))
    )
    (net (code "139") (name "Net-(USE-VINA+)") (class "Default")
      (node (ref "R10") (pin "2") (pinfunction "2_2") (pintype "passive"))
      (node (ref "R11") (pin "1") (pinfunction "1_1") (pintype "passive"))
      (node (ref "USE") (pin "3") (pinfunction "VINA+_3") (pintype "input"))
    )
    (net (code "140") (name "Net-(USE-VINB-)") (class "Default")
      (node (ref "R11") (pin "2") (pinfunction "2_2") (pintype "passive"))
      (node (ref "R12") (pin "1") (pinfunction "1_1") (pintype "passive"))
      (node (ref "USE") (pin "6") (pinfunction "VINB-_6") (pintype "input"))
    )
    (net (code "141") (name "Net-(USS-VINA+)") (class "Default")
      (node (ref "R13") (pin "2") (pinfunction "2_2") (pintype "passive"))
      (node (ref "R14") (pin "1") (pinfunction "1_1") (pintype "passive"))
      (node (ref "USS") (pin "3") (pinfunction "VINA+_3") (pintype "input"))
    )
    (net (code "142") (name "Net-(USS-VINB-)") (class "Default")
      (node (ref "R14") (pin "2") (pinfunction "2_2") (pintype "passive"))
      (node (ref "R15") (pin "1") (pinfunction "1_1") (pintype "passive"))
      (node (ref "USS") (pin "6") (pinfunction "VINB-_6") (pintype "input"))
    )
    (net (code "143") (name "Net-(USW-VINA+)") (class "Default")
      (node (ref "R16") (pin "2") (pinfunction "2_2") (pintype "passive"))
      (node (ref "R17") (pin "1") (pinfunction "1_1") (pintype "passive"))
      (node (ref "USW") (pin "3") (pinfunction "VINA+_3") (pintype "input"))
    )
    (net (code "144") (name "Net-(USW-VINB-)") (class "Default")
      (node (ref "R17") (pin "2") (pinfunction "2_2") (pintype "passive"))
      (node (ref "R18") (pin "1") (pinfunction "1_1") (pintype "passive"))
      (node (ref "USW") (pin "6") (pinfunction "VINB-_6") (pintype "input"))
    )
    (net (code "145") (name "S00_N") (class "Default")
      (node (ref "X-SOUTH") (pin "16") (pinfunction "16_16") (pintype "bidirectional"))
    )
    (net (code "146") (name "S00_P") (class "Default")
      (node (ref "X-SOUTH") (pin "14") (pinfunction "14_14") (pintype "bidirectional"))
    )
    (net (code "147") (name "S01_N") (class "Default")
      (node (ref "X-SOUTH") (pin "17") (pinfunction "17_17") (pintype "bidirectional"))
    )
    (net (code "148") (name "S01_P") (class "Default")
      (node (ref "X-SOUTH") (pin "15") (pinfunction "15_15") (pintype "bidirectional"))
    )
    (net (code "149") (name "S02_N") (class "Default")
      (node (ref "X-SOUTH") (pin "22") (pinfunction "22_22") (pintype "bidirectional"))
    )
    (net (code "150") (name "S02_P") (class "Default")
      (node (ref "X-SOUTH") (pin "20") (pinfunction "20_20") (pintype "bidirectional"))
    )
    (net (code "151") (name "S03_N") (class "Default")
      (node (ref "X-SOUTH") (pin "23") (pinfunction "23_23") (pintype "bidirectional"))
    )
    (net (code "152") (name "S03_P") (class "Default")
      (node (ref "X-SOUTH") (pin "21") (pinfunction "21_21") (pintype "bidirectional"))
    )
    (net (code "153") (name "S04_N") (class "Default")
      (node (ref "SENSOR") (pin "C24") (pinfunction "OUT32_N_C24") (pintype "output"))
      (node (ref "X-SOUTH") (pin "28") (pinfunction "28_28") (pintype "bidirectional"))
    )
    (net (code "154") (name "S04_P") (class "Default")
      (node (ref "SENSOR") (pin "C25") (pinfunction "OUT32_P_C25") (pintype "output"))
      (node (ref "X-SOUTH") (pin "26") (pinfunction "26_26") (pintype "bidirectional"))
    )
    (net (code "155") (name "S05_N") (class "Default")
      (node (ref "X-SOUTH") (pin "29") (pinfunction "29_29") (pintype "bidirectional"))
    )
    (net (code "156") (name "S05_P") (class "Default")
      (node (ref "X-SOUTH") (pin "27") (pinfunction "27_27") (pintype "bidirectional"))
    )
    (net (code "157") (name "S06_N") (class "Default")
      (node (ref "SENSOR") (pin "D23") (pinfunction "OUT30_N_D23") (pintype "output"))
      (node (ref "X-SOUTH") (pin "34") (pinfunction "34_34") (pintype "bidirectional"))
    )
    (net (code "158") (name "S06_P") (class "Default")
      (node (ref "SENSOR") (pin "D24") (pinfunction "OUT30_P_D24") (pintype "output"))
      (node (ref "X-SOUTH") (pin "32") (pinfunction "32_32") (pintype "bidirectional"))
    )
    (net (code "159") (name "S07_N") (class "Default")
      (node (ref "SENSOR") (pin "B24") (pinfunction "OUT31_N_B24") (pintype "output"))
      (node (ref "X-SOUTH") (pin "35") (pinfunction "35_35") (pintype "bidirectional"))
    )
    (net (code "160") (name "S07_P") (class "Default")
      (node (ref "SENSOR") (pin "B25") (pinfunction "OUT31_P_B25") (pintype "output"))
      (node (ref "X-SOUTH") (pin "33") (pinfunction "33_33") (pintype "bidirectional"))
    )
    (net (code "161") (name "S08_N") (class "Default")
      (node (ref "SENSOR") (pin "D21") (pinfunction "OUT27_N_D21") (pintype "output"))
      (node (ref "X-SOUTH") (pin "40") (pinfunction "40_40") (pintype "bidirectional"))
    )
    (net (code "162") (name "S08_P") (class "Default")
      (node (ref "SENSOR") (pin "D22") (pinfunction "OUT27_P_D22") (pintype "output"))
      (node (ref "X-SOUTH") (pin "38") (pinfunction "38_38") (pintype "bidirectional"))
    )
    (net (code "163") (name "S09_N") (class "Default")
      (node (ref "SENSOR") (pin "A23") (pinfunction "OUT29_N_A23") (pintype "output"))
      (node (ref "X-SOUTH") (pin "41") (pinfunction "41_41") (pintype "bidirectional"))
    )
    (net (code "164") (name "S09_P") (class "Default")
      (node (ref "SENSOR") (pin "A24") (pinfunction "OUT29_P_A24") (pintype "output"))
      (node (ref "X-SOUTH") (pin "39") (pinfunction "39_39") (pintype "bidirectional"))
    )
    (net (code "165") (name "S10_N") (class "Default")
      (node (ref "SENSOR") (pin "C21") (pinfunction "OUT28_N_C21") (pintype "output"))
      (node (ref "X-SOUTH") (pin "46") (pinfunction "46_46") (pintype "bidirectional"))
    )
    (net (code "166") (name "S10_P") (class "Default")
      (node (ref "SENSOR") (pin "C22") (pinfunction "OUT28_P_C22") (pintype "output"))
      (node (ref "X-SOUTH") (pin "44") (pinfunction "44_44") (pintype "bidirectional"))
    )
    (net (code "167") (name "S11_N") (class "Default")
      (node (ref "SENSOR") (pin "B20") (pinfunction "OUT26_N_B20") (pintype "output"))
      (node (ref "X-SOUTH") (pin "47") (pinfunction "47_47") (pintype "bidirectional"))
    )
    (net (code "168") (name "S11_P") (class "Default")
      (node (ref "SENSOR") (pin "B21") (pinfunction "OUT26_P_B21") (pintype "output"))
      (node (ref "X-SOUTH") (pin "45") (pinfunction "45_45") (pintype "bidirectional"))
    )
    (net (code "169") (name "S12_N") (class "Default")
      (node (ref "SENSOR") (pin "D19") (pinfunction "OUT24_N_D19") (pintype "output"))
      (node (ref "X-SOUTH") (pin "52") (pinfunction "52_52") (pintype "bidirectional"))
    )
    (net (code "170") (name "S12_P") (class "Default")
      (node (ref "SENSOR") (pin "D20") (pinfunction "OUT24_P_D20") (pintype "output"))
      (node (ref "X-SOUTH") (pin "50") (pinfunction "50_50") (pintype "bidirectional"))
    )
    (net (code "171") (name "S13_N") (class "Default")
      (node (ref "SENSOR") (pin "A19") (pinfunction "OUT23_N_A19") (pintype "output"))
      (node (ref "X-SOUTH") (pin "53") (pinfunction "53_53") (pintype "bidirectional"))
    )
    (net (code "172") (name "S13_P") (class "Default")
      (node (ref "SENSOR") (pin "A20") (pinfunction "OUT23_P_A20") (pintype "output"))
      (node (ref "X-SOUTH") (pin "51") (pinfunction "51_51") (pintype "bidirectional"))
    )
    (net (code "173") (name "S14_N") (class "Default")
      (node (ref "SENSOR") (pin "C19") (pinfunction "OUT25_N_C19") (pintype "output"))
      (node (ref "X-SOUTH") (pin "58") (pinfunction "58_58") (pintype "bidirectional"))
    )
    (net (code "174") (name "S14_P") (class "Default")
      (node (ref "SENSOR") (pin "C20") (pinfunction "OUT25_P_C20") (pintype "output"))
      (node (ref "X-SOUTH") (pin "56") (pinfunction "56_56") (pintype "bidirectional"))
    )
    (net (code "175") (name "S15_N") (class "Default")
      (node (ref "SENSOR") (pin "B18") (pinfunction "OUT22_N_B18") (pintype "output"))
      (node (ref "X-SOUTH") (pin "59") (pinfunction "59_59") (pintype "bidirectional"))
    )
    (net (code "176") (name "S15_P") (class "Default")
      (node (ref "SENSOR") (pin "B19") (pinfunction "OUT22_P_B19") (pintype "output"))
      (node (ref "X-SOUTH") (pin "57") (pinfunction "57_57") (pintype "bidirectional"))
    )
    (net (code "177") (name "S16_N") (class "Default")
      (node (ref "SENSOR") (pin "C17") (pinfunction "OUT21_N_C17") (pintype "output"))
      (node (ref "X-SOUTH") (pin "64") (pinfunction "64_64") (pintype "bidirectional"))
    )
    (net (code "178") (name "S16_P") (class "Default")
      (node (ref "SENSOR") (pin "C18") (pinfunction "OUT21_P_C18") (pintype "output"))
      (node (ref "X-SOUTH") (pin "62") (pinfunction "62_62") (pintype "bidirectional"))
    )
    (net (code "179") (name "S17_N") (class "Default")
      (node (ref "SENSOR") (pin "A17") (pinfunction "OUT19_N_A17") (pintype "output"))
      (node (ref "X-SOUTH") (pin "65") (pinfunction "65_65") (pintype "bidirectional"))
    )
    (net (code "180") (name "S17_P") (class "Default")
      (node (ref "SENSOR") (pin "A18") (pinfunction "OUT19_P_A18") (pintype "output"))
      (node (ref "X-SOUTH") (pin "63") (pinfunction "63_63") (pintype "bidirectional"))
    )
    (net (code "181") (name "S18_N") (class "Default")
      (node (ref "SENSOR") (pin "D17") (pinfunction "OUT20_N_D17") (pintype "output"))
      (node (ref "X-SOUTH") (pin "70") (pinfunction "70_70") (pintype "bidirectional"))
    )
    (net (code "182") (name "S18_P") (class "Default")
      (node (ref "SENSOR") (pin "D18") (pinfunction "OUT20_P_D18") (pintype "output"))
      (node (ref "X-SOUTH") (pin "68") (pinfunction "68_68") (pintype "bidirectional"))
    )
    (net (code "183") (name "S19_N") (class "Default")
      (node (ref "SENSOR") (pin "B16") (pinfunction "OUT18_N_B16") (pintype "output"))
      (node (ref "X-SOUTH") (pin "71") (pinfunction "71_71") (pintype "bidirectional"))
    )
    (net (code "184") (name "S19_P") (class "Default")
      (node (ref "SENSOR") (pin "B17") (pinfunction "OUT18_P_B17") (pintype "output"))
      (node (ref "X-SOUTH") (pin "69") (pinfunction "69_69") (pintype "bidirectional"))
    )
    (net (code "185") (name "S20_N") (class "Default")
      (node (ref "SENSOR") (pin "D15") (pinfunction "OUT17_N_D15") (pintype "output"))
      (node (ref "X-SOUTH") (pin "76") (pinfunction "76_76") (pintype "bidirectional"))
    )
    (net (code "186") (name "S20_P") (class "Default")
      (node (ref "SENSOR") (pin "D16") (pinfunction "OUT17_P_D16") (pintype "output"))
      (node (ref "X-SOUTH") (pin "74") (pinfunction "74_74") (pintype "bidirectional"))
    )
    (net (code "187") (name "S21_N") (class "Default")
      (node (ref "SENSOR") (pin "B14") (pinfunction "OUT16_N_B14") (pintype "output"))
      (node (ref "X-SOUTH") (pin "77") (pinfunction "77_77") (pintype "bidirectional"))
    )
    (net (code "188") (name "S21_P") (class "Default")
      (node (ref "SENSOR") (pin "B15") (pinfunction "OUT16_P_B15") (pintype "output"))
      (node (ref "X-SOUTH") (pin "75") (pinfunction "75_75") (pintype "bidirectional"))
    )
    (net (code "189") (name "S22_N") (class "Default")
      (node (ref "SENSOR") (pin "D13") (pinfunction "OUT15_N_D13") (pintype "output"))
      (node (ref "X-SOUTH") (pin "82") (pinfunction "82_82") (pintype "bidirectional"))
    )
    (net (code "190") (name "S22_P") (class "Default")
      (node (ref "SENSOR") (pin "D14") (pinfunction "OUT15_P_D14") (pintype "output"))
      (node (ref "X-SOUTH") (pin "80") (pinfunction "80_80") (pintype "bidirectional"))
    )
    (net (code "191") (name "S23_N") (class "Default")
      (node (ref "SENSOR") (pin "A13") (pinfunction "OUT13_N_A13") (pintype "output"))
      (node (ref "X-SOUTH") (pin "83") (pinfunction "83_83") (pintype "bidirectional"))
    )
    (net (code "192") (name "S23_P") (class "Default")
      (node (ref "SENSOR") (pin "A14") (pinfunction "OUT13_P_A14") (pintype "output"))
      (node (ref "X-SOUTH") (pin "81") (pinfunction "81_81") (pintype "bidirectional"))
    )
    (net (code "193") (name "S24_N") (class "Default")
      (node (ref "SENSOR") (pin "C13") (pinfunction "OUT14_N_C13") (pintype "output"))
      (node (ref "X-SOUTH") (pin "88") (pinfunction "88_88") (pintype "bidirectional"))
    )
    (net (code "194") (name "S24_P") (class "Default")
      (node (ref "SENSOR") (pin "C14") (pinfunction "OUT14_P_C14") (pintype "output"))
      (node (ref "X-SOUTH") (pin "86") (pinfunction "86_86") (pintype "bidirectional"))
    )
    (net (code "195") (name "S25_N") (class "Default")
      (node (ref "SENSOR") (pin "B12") (pinfunction "OUT12_N_B12") (pintype "output"))
      (node (ref "X-SOUTH") (pin "89") (pinfunction "89_89") (pintype "bidirectional"))
    )
    (net (code "196") (name "S25_P") (class "Default")
      (node (ref "SENSOR") (pin "B13") (pinfunction "OUT12_P_B13") (pintype "output"))
      (node (ref "X-SOUTH") (pin "87") (pinfunction "87_87") (pintype "bidirectional"))
    )
    (net (code "197") (name "S26_N") (class "Default")
      (node (ref "SENSOR") (pin "D11") (pinfunction "OUT10_N_D11") (pintype "output"))
      (node (ref "X-SOUTH") (pin "94") (pinfunction "94_94") (pintype "bidirectional"))
    )
    (net (code "198") (name "S26_P") (class "Default")
      (node (ref "SENSOR") (pin "D12") (pinfunction "OUT10_P_D12") (pintype "output"))
      (node (ref "X-SOUTH") (pin "92") (pinfunction "92_92") (pintype "bidirectional"))
    )
    (net (code "199") (name "S27_N") (class "Default")
      (node (ref "SENSOR") (pin "A11") (pinfunction "OUT9_N_A11") (pintype "output"))
      (node (ref "X-SOUTH") (pin "95") (pinfunction "95_95") (pintype "bidirectional"))
    )
    (net (code "200") (name "S27_P") (class "Default")
      (node (ref "SENSOR") (pin "A12") (pinfunction "OUT9_P_A12") (pintype "output"))
      (node (ref "X-SOUTH") (pin "93") (pinfunction "93_93") (pintype "bidirectional"))
    )
    (net (code "201") (name "S28_N") (class "Default")
      (node (ref "SENSOR") (pin "C11") (pinfunction "OUT11_N_C11") (pintype "output"))
      (node (ref "X-SOUTH") (pin "100") (pinfunction "100_100") (pintype "bidirectional"))
    )
    (net (code "202") (name "S28_P") (class "Default")
      (node (ref "SENSOR") (pin "C12") (pinfunction "OUT11_P_C12") (pintype "output"))
      (node (ref "X-SOUTH") (pin "98") (pinfunction "98_98") (pintype "bidirectional"))
    )
    (net (code "203") (name "S29_N") (class "Default")
      (node (ref "SENSOR") (pin "B10") (pinfunction "OUT8_N_B10") (pintype "output"))
      (node (ref "X-SOUTH") (pin "101") (pinfunction "101_101") (pintype "bidirectional"))
    )
    (net (code "204") (name "S29_P") (class "Default")
      (node (ref "SENSOR") (pin "B11") (pinfunction "OUT8_P_B11") (pintype "output"))
      (node (ref "X-SOUTH") (pin "99") (pinfunction "99_99") (pintype "bidirectional"))
    )
    (net (code "205") (name "S30_N") (class "Default")
      (node (ref "SENSOR") (pin "C9") (pinfunction "OUT7_N_C9") (pintype "output"))
      (node (ref "X-SOUTH") (pin "106") (pinfunction "106_106") (pintype "bidirectional"))
    )
    (net (code "206") (name "S30_P") (class "Default")
      (node (ref "SENSOR") (pin "C10") (pinfunction "OUT7_P_C10") (pintype "output"))
      (node (ref "X-SOUTH") (pin "104") (pinfunction "104_104") (pintype "bidirectional"))
    )
    (net (code "207") (name "S31_N") (class "Default")
      (node (ref "SENSOR") (pin "B8") (pinfunction "OUT5_N_B8") (pintype "output"))
      (node (ref "X-SOUTH") (pin "107") (pinfunction "107_107") (pintype "bidirectional"))
    )
    (net (code "208") (name "S31_P") (class "Default")
      (node (ref "SENSOR") (pin "B9") (pinfunction "OUT5_P_B9") (pintype "output"))
      (node (ref "X-SOUTH") (pin "105") (pinfunction "105_105") (pintype "bidirectional"))
    )
    (net (code "209") (name "S32_N") (class "Default")
      (node (ref "SENSOR") (pin "D9") (pinfunction "OUT6_N_D9") (pintype "output"))
      (node (ref "X-SOUTH") (pin "112") (pinfunction "112_112") (pintype "bidirectional"))
    )
    (net (code "210") (name "S32_P") (class "Default")
      (node (ref "SENSOR") (pin "D10") (pinfunction "OUT6_P_D10") (pintype "output"))
      (node (ref "X-SOUTH") (pin "110") (pinfunction "110_110") (pintype "bidirectional"))
    )
    (net (code "211") (name "S33_N") (class "Default")
      (node (ref "SENSOR") (pin "A7") (pinfunction "OUT2_N_A7") (pintype "output"))
      (node (ref "X-SOUTH") (pin "113") (pinfunction "113_113") (pintype "bidirectional"))
    )
    (net (code "212") (name "S33_P") (class "Default")
      (node (ref "SENSOR") (pin "A8") (pinfunction "OUT2_P_A8") (pintype "output"))
      (node (ref "X-SOUTH") (pin "111") (pinfunction "111_111") (pintype "bidirectional"))
    )
    (net (code "213") (name "S34_N") (class "Default")
      (node (ref "SENSOR") (pin "C7") (pinfunction "OUT4_N_C7") (pintype "output"))
      (node (ref "X-SOUTH") (pin "118") (pinfunction "118_118") (pintype "bidirectional"))
    )
    (net (code "214") (name "S34_P") (class "Default")
      (node (ref "SENSOR") (pin "C8") (pinfunction "OUT4_P_C8") (pintype "output"))
      (node (ref "X-SOUTH") (pin "116") (pinfunction "116_116") (pintype "bidirectional"))
    )
    (net (code "215") (name "S35_N") (class "Default")
      (node (ref "SENSOR") (pin "B6") (pinfunction "OUT1_N_B6") (pintype "output"))
      (node (ref "X-SOUTH") (pin "119") (pinfunction "119_119") (pintype "bidirectional"))
    )
    (net (code "216") (name "S35_P") (class "Default")
      (node (ref "SENSOR") (pin "B7") (pinfunction "OUT1_P_B7") (pintype "output"))
      (node (ref "X-SOUTH") (pin "117") (pinfunction "117_117") (pintype "bidirectional"))
    )
    (net (code "217") (name "S36_N") (class "Default")
      (node (ref "SENSOR") (pin "D7") (pinfunction "OUT3_N_D7") (pintype "output"))
      (node (ref "X-SOUTH") (pin "124") (pinfunction "124_124") (pintype "bidirectional"))
    )
    (net (code "218") (name "S36_P") (class "Default")
      (node (ref "SENSOR") (pin "D8") (pinfunction "OUT3_P_D8") (pintype "output"))
      (node (ref "X-SOUTH") (pin "122") (pinfunction "122_122") (pintype "bidirectional"))
    )
    (net (code "219") (name "S37_N") (class "Default")
      (node (ref "SENSOR") (pin "A5") (pinfunction "OUTCTR_N_A5") (pintype "output"))
      (node (ref "X-SOUTH") (pin "125") (pinfunction "125_125") (pintype "bidirectional"))
    )
    (net (code "220") (name "S37_P") (class "Default")
      (node (ref "SENSOR") (pin "A6") (pinfunction "OUTCTR_P_A6") (pintype "output"))
      (node (ref "X-SOUTH") (pin "123") (pinfunction "123_123") (pintype "bidirectional"))
    )
    (net (code "221") (name "S38_N") (class "Default")
      (node (ref "X-SOUTH") (pin "130") (pinfunction "130_130") (pintype "bidirectional"))
    )
    (net (code "222") (name "S38_P") (class "Default")
      (node (ref "X-SOUTH") (pin "128") (pinfunction "128_128") (pintype "bidirectional"))
    )
    (net (code "223") (name "S39_N") (class "Default")
      (node (ref "U3") (pin "6") (pinfunction "EN_6") (pintype "input"))
      (node (ref "X-SOUTH") (pin "131") (pinfunction "131_131") (pintype "bidirectional"))
    )
    (net (code "224") (name "S39_P") (class "Default")
      (node (ref "X-SOUTH") (pin "129") (pinfunction "129_129") (pintype "bidirectional"))
    )
    (net (code "225") (name "SPI_CLK") (class "Default")
      (node (ref "SENSOR") (pin "H29") (pinfunction "SPI_CLK_H29") (pintype "input"))
      (node (ref "U4") (pin "6") (pinfunction "1A1_6") (pintype "output"))
    )
    (net (code "226") (name "SPI_EN") (class "Default")
      (node (ref "SENSOR") (pin "F28") (pinfunction "SPI_EN_F28") (pintype "input"))
      (node (ref "U6") (pin "9") (pinfunction "B4_9") (pintype "bidirectional"))
    )
    (net (code "227") (name "SPI_IN") (class "Default")
      (node (ref "SENSOR") (pin "E28") (pinfunction "SPI_IN_E28") (pintype "input"))
      (node (ref "U4") (pin "7") (pinfunction "1A2_7") (pintype "output"))
    )
    (net (code "228") (name "SPI_OUT") (class "Default")
      (node (ref "SENSOR") (pin "G28") (pinfunction "SPI_OUT_G28") (pintype "output"))
      (node (ref "U4") (pin "8") (pinfunction "2A1_8") (pintype "output"))
    )
    (net (code "229") (name "SYS_RES_N") (class "Default")
      (node (ref "SENSOR") (pin "F30") (pinfunction "SYS_RES_N_F30") (pintype "input"))
      (node (ref "U5") (pin "10") (pinfunction "B3_10") (pintype "bidirectional"))
    )
    (net (code "230") (name "S_CHK_V") (class "Default")
      (node (ref "C5") (pin "1") (pinfunction "1_1") (pintype "passive"))
      (node (ref "C6") (pin "1") (pinfunction "1_1") (pintype "passive"))
      (node (ref "C7") (pin "1") (pinfunction "1_1") (pintype "passive"))
      (node (ref "R20") (pin "1") (pinfunction "1_1") (pintype "passive"))
      (node (ref "TP3") (pin "TP") (pinfunction "TP_TP") (pintype "input"))
      (node (ref "USE") (pin "8") (pinfunction "VDD_8") (pintype "power_in"))
      (node (ref "USS") (pin "8") (pinfunction "VDD_8") (pintype "power_in"))
      (node (ref "USW") (pin "8") (pinfunction "VDD_8") (pintype "power_in"))
      (node (ref "X-SOUTH") (pin "10") (pinfunction "10_10") (pintype "bidirectional"))
      (node (ref "X-SOUTH") (pin "8") (pinfunction "8_8") (pintype "bidirectional"))
    )
    (net (code "231") (name "S_I2C_V") (class "Default")
      (node (ref "X-SOUTH") (pin "135") (pinfunction "135_135") (pintype "bidirectional"))
      (node (ref "X-SOUTH") (pin "137") (pinfunction "137_137") (pintype "bidirectional"))
    )
    (net (code "232") (name "S_REF") (class "Default")
      (node (ref "R20") (pin "2") (pinfunction "2_2") (pintype "passive"))
      (node (ref "TP4") (pin "TP") (pinfunction "TP_TP") (pintype "input"))
      (node (ref "U2") (pin "3") (pinfunction "CATHODE_3") (pintype "output"))
      (node (ref "U2") (pin "4") (pinfunction "REF_4") (pintype "input"))
      (node (ref "USE") (pin "2") (pinfunction "VINA-_2") (pintype "input"))
      (node (ref "USE") (pin "5") (pinfunction "VINB+_5") (pintype "input"))
      (node (ref "USS") (pin "2") (pinfunction "VINA-_2") (pintype "input"))
      (node (ref "USS") (pin "5") (pinfunction "VINB+_5") (pintype "input"))
      (node (ref "USW") (pin "2") (pinfunction "VINA-_2") (pintype "input"))
      (node (ref "USW") (pin "5") (pinfunction "VINB+_5") (pintype "input"))
    )
    (net (code "233") (name "S_SCK") (class "Default")
      (node (ref "X-SOUTH") (pin "144") (pinfunction "144_144") (pintype "bidirectional"))
    )
    (net (code "234") (name "S_SCL") (class "Default")
      (node (ref "X-SOUTH") (pin "143") (pinfunction "143_143") (pintype "bidirectional"))
    )
    (net (code "235") (name "S_SDA") (class "Default")
      (node (ref "X-SOUTH") (pin "141") (pinfunction "141_141") (pintype "bidirectional"))
    )
    (net (code "236") (name "S_SDI") (class "Default")
      (node (ref "X-SOUTH") (pin "140") (pinfunction "140_140") (pintype "bidirectional"))
    )
    (net (code "237") (name "S_SDO") (class "Default")
      (node (ref "X-SOUTH") (pin "142") (pinfunction "142_142") (pintype "bidirectional"))
    )
    (net (code "238") (name "S_SPI_V") (class "Default")
      (node (ref "X-SOUTH") (pin "134") (pinfunction "134_134") (pintype "bidirectional"))
      (node (ref "X-SOUTH") (pin "136") (pinfunction "136_136") (pintype "bidirectional"))
    )
    (net (code "239") (name "S_VE") (class "Default")
      (node (ref "X-SOUTH") (pin "13") (pinfunction "13_13") (pintype "bidirectional"))
      (node (ref "X-SOUTH") (pin "19") (pinfunction "19_19") (pintype "bidirectional"))
      (node (ref "X-SOUTH") (pin "25") (pinfunction "25_25") (pintype "bidirectional"))
      (node (ref "X-SOUTH") (pin "31") (pinfunction "31_31") (pintype "bidirectional"))
      (node (ref "X-SOUTH") (pin "37") (pinfunction "37_37") (pintype "bidirectional"))
    )
    (net (code "240") (name "S_VE_CV") (class "Default")
      (node (ref "C11") (pin "1") (pinfunction "1_1") (pintype "passive"))
      (node (ref "R10") (pin "1") (pinfunction "1_1") (pintype "passive"))
      (node (ref "X-SOUTH") (pin "2") (pinfunction "2_2") (pintype "bidirectional"))
    )
    (net (code "241") (name "S_VE_OV") (class "Default")
      (node (ref "USE") (pin "7") (pinfunction "OUTB_7") (pintype "output"))
      (node (ref "X-SOUTH") (pin "1") (pinfunction "1_1") (pintype "bidirectional"))
    )
    (net (code "242") (name "S_VE_UV") (class "Default")
      (node (ref "USE") (pin "1") (pinfunction "OUTA_1") (pintype "output"))
      (node (ref "X-SOUTH") (pin "7") (pinfunction "7_7") (pintype "bidirectional"))
    )
    (net (code "243") (name "S_VS") (class "Default")
      (node (ref "C45") (pin "1") (pinfunction "1_1") (pintype "passive"))
      (node (ref "C46") (pin "1") (pinfunction "1_1") (pintype "passive"))
      (node (ref "C47") (pin "1") (pinfunction "1_1") (pintype "passive"))
      (node (ref "C48") (pin "1") (pinfunction "1_1") (pintype "passive"))
      (node (ref "C49") (pin "1") (pinfunction "1_1") (pintype "passive"))
      (node (ref "C72") (pin "1") (pinfunction "1_1") (pintype "passive"))
      (node (ref "C73") (pin "1") (pinfunction "1_1") (pintype "passive"))
      (node (ref "C74") (pin "1") (pinfunction "1_1") (pintype "passive"))
      (node (ref "C81") (pin "1") (pinfunction "1_1") (pintype "passive"))
      (node (ref "C82") (pin "1") (pinfunction "1_1") (pintype "passive"))
      (node (ref "C83") (pin "1") (pinfunction "1_1") (pintype "passive"))
      (node (ref "SENSOR") (pin "A30") (pinfunction "VDD_PIX_A30") (pintype "power_in"))
      (node (ref "SENSOR") (pin "D28") (pinfunction "VDD_PIX_D28") (pintype "power_in"))
      (node (ref "SENSOR") (pin "D30") (pinfunction "VDD_PIX_D30") (pintype "power_in"))
      (node (ref "SENSOR") (pin "G1") (pinfunction "VDD_PIX_G1") (pintype "power_in"))
      (node (ref "SENSOR") (pin "H28") (pinfunction "VDD_PIX_H28") (pintype "power_in"))
      (node (ref "TP6") (pin "TP") (pinfunction "TP_TP") (pintype "input"))
      (node (ref "X-SOUTH") (pin "49") (pinfunction "49_49") (pintype "bidirectional"))
      (node (ref "X-SOUTH") (pin "55") (pinfunction "55_55") (pintype "bidirectional"))
      (node (ref "X-SOUTH") (pin "61") (pinfunction "61_61") (pintype "bidirectional"))
      (node (ref "X-SOUTH") (pin "67") (pinfunction "67_67") (pintype "bidirectional"))
      (node (ref "X-SOUTH") (pin "73") (pinfunction "73_73") (pintype "bidirectional"))
      (node (ref "X-SOUTH") (pin "79") (pinfunction "79_79") (pintype "bidirectional"))
      (node (ref "X-SOUTH") (pin "85") (pinfunction "85_85") (pintype "bidirectional"))
      (node (ref "X-SOUTH") (pin "91") (pinfunction "91_91") (pintype "bidirectional"))
      (node (ref "X-SOUTH") (pin "97") (pinfunction "97_97") (pintype "bidirectional"))
    )
    (net (code "244") (name "S_VS_CV") (class "Default")
      (node (ref "C12") (pin "1") (pinfunction "1_1") (pintype "passive"))
      (node (ref "R13") (pin "1") (pinfunction "1_1") (pintype "passive"))
      (node (ref "X-SOUTH") (pin "4") (pinfunction "4_4") (pintype "bidirectional"))
    )
    (net (code "245") (name "S_VS_OV") (class "Default")
      (node (ref "USS") (pin "7") (pinfunction "OUTB_7") (pintype "output"))
      (node (ref "X-SOUTH") (pin "3") (pinfunction "3_3") (pintype "bidirectional"))
    )
    (net (code "246") (name "S_VS_UV") (class "Default")
      (node (ref "USS") (pin "1") (pinfunction "OUTA_1") (pintype "output"))
      (node (ref "X-SOUTH") (pin "9") (pinfunction "9_9") (pintype "bidirectional"))
    )
    (net (code "247") (name "S_VW") (class "Default")
      (node (ref "C90") (pin "1") (pinfunction "1_1") (pintype "passive"))
      (node (ref "U3") (pin "1") (pinfunction "BIAS_1") (pintype "power_in"))
      (node (ref "U3") (pin "3") (pinfunction "IN_3") (pintype "power_in"))
      (node (ref "X-SOUTH") (pin "109") (pinfunction "109_109") (pintype "bidirectional"))
      (node (ref "X-SOUTH") (pin "115") (pinfunction "115_115") (pintype "bidirectional"))
      (node (ref "X-SOUTH") (pin "121") (pinfunction "121_121") (pintype "bidirectional"))
      (node (ref "X-SOUTH") (pin "127") (pinfunction "127_127") (pintype "bidirectional"))
      (node (ref "X-SOUTH") (pin "133") (pinfunction "133_133") (pintype "bidirectional"))
    )
    (net (code "248") (name "S_VW_CV") (class "Default")
      (node (ref "C13") (pin "1") (pinfunction "1_1") (pintype "passive"))
      (node (ref "R16") (pin "1") (pinfunction "1_1") (pintype "passive"))
      (node (ref "X-SOUTH") (pin "6") (pinfunction "6_6") (pintype "bidirectional"))
    )
    (net (code "249") (name "S_VW_OV") (class "Default")
      (node (ref "USW") (pin "7") (pinfunction "OUTB_7") (pintype "output"))
      (node (ref "X-SOUTH") (pin "5") (pinfunction "5_5") (pintype "bidirectional"))
    )
    (net (code "250") (name "S_VW_UV") (class "Default")
      (node (ref "USW") (pin "1") (pinfunction "OUTA_1") (pintype "output"))
      (node (ref "X-SOUTH") (pin "11") (pinfunction "11_11") (pintype "bidirectional"))
    )
    (net (code "251") (name "TDIG1") (class "Default")
      (node (ref "SENSOR") (pin "G27") (pinfunction "TDIG1_G27") (pintype "output"))
      (node (ref "U5") (pin "9") (pinfunction "B4_9") (pintype "bidirectional"))
    )
    (net (code "252") (name "TDIG2") (class "Default")
      (node (ref "SENSOR") (pin "G26") (pinfunction "TDIG2_G26") (pintype "output"))
      (node (ref "U6") (pin "11") (pinfunction "B2_11") (pintype "bidirectional"))
    )
    (net (code "253") (name "T_EXP1") (class "Default")
      (node (ref "SENSOR") (pin "H30") (pinfunction "T_EXP1_H30") (pintype "input"))
      (node (ref "U5") (pin "12") (pinfunction "B1_12") (pintype "bidirectional"))
    )
    (net (code "254") (name "T_EXP2") (class "Default")
      (node (ref "SENSOR") (pin "E29") (pinfunction "T_EXP2_E29") (pintype "input"))
      (node (ref "U6") (pin "10") (pinfunction "B3_10") (pintype "bidirectional"))
    )
    (net (code "255") (name "VRAMP1") (class "Default")
      (node (ref "C16") (pin "1") (pinfunction "1_1") (pintype "passive"))
      (node (ref "R23") (pin "1") (pinfunction "1_1") (pintype "passive"))
      (node (ref "SENSOR") (pin "G29") (pinfunction "VRAMP1_G29") (pintype "bidirectional"))
    )
    (net (code "256") (name "VRAMP2") (class "Default")
      (node (ref "C17") (pin "1") (pinfunction "1_1") (pintype "passive"))
      (node (ref "R23") (pin "2") (pinfunction "2_2") (pintype "passive"))
      (node (ref "SENSOR") (pin "F29") (pinfunction "VRAMP2_F29") (pintype "bidirectional"))
    )
    (net (code "257") (name "VTREF") (class "Default")
      (node (ref "C65") (pin "1") (pinfunction "1_1") (pintype "passive"))
      (node (ref "C91") (pin "2") (pinfunction "2_2") (pintype "passive"))
      (node (ref "R21") (pin "2") (pinfunction "2_2") (pintype "passive"))
      (node (ref "R24") (pin "1") (pinfunction "1_1") (pintype "passive"))
      (node (ref "SENSOR") (pin "B2") (pinfunction "VTREF_B2") (pintype "bidirectional"))
      (node (ref "U3") (pin "4") (pinfunction "OUT_4") (pintype "power_in"))
    )
    (net (code "258") (name "VTSIG") (class "Default")
      (node (ref "C66") (pin "1") (pinfunction "1_1") (pintype "passive"))
      (node (ref "R24") (pin "2") (pinfunction "2_2") (pintype "passive"))
      (node (ref "SENSOR") (pin "C2") (pinfunction "VTSIG_C2") (pintype "bidirectional"))
    )
    (net (code "259") (name "unconnected-(U1-NC-Pad1)") (class "Default")
      (node (ref "U1") (pin "1") (pinfunction "NC_1") (pintype "no_connect"))
    )
    (net (code "260") (name "unconnected-(U1-NC-Pad2)") (class "Default")
      (node (ref "U1") (pin "2") (pinfunction "NC_2") (pintype "no_connect"))
    )
    (net (code "261") (name "unconnected-(U2-NC-Pad1)") (class "Default")
      (node (ref "U2") (pin "1") (pinfunction "NC_1") (pintype "no_connect"))
    )
    (net (code "262") (name "unconnected-(U2-NC-Pad2)") (class "Default")
      (node (ref "U2") (pin "2") (pinfunction "NC_2") (pintype "no_connect"))
    )
    (net (code "263") (name "unconnected-(U4-2B2-Pad12)") (class "Default")
      (node (ref "U4") (pin "12") (pinfunction "2B2_12") (pintype "output"))
    )
    (net (code "264") (name "unconnected-(X-NORTH-PadM1)") (class "Default")
      (node (ref "X-NORTH") (pin "M1") (pinfunction "M1_M1") (pintype "bidirectional"))
    )
    (net (code "265") (name "unconnected-(X-NORTH-PadM2)") (class "Default")
      (node (ref "X-NORTH") (pin "M2") (pinfunction "M2_M2") (pintype "bidirectional"))
    )
    (net (code "266") (name "unconnected-(X-SOUTH-PadM1)") (class "Default")
      (node (ref "X-SOUTH") (pin "M1") (pinfunction "M1_M1") (pintype "bidirectional"))
    )
    (net (code "267") (name "unconnected-(X-SOUTH-PadM2)") (class "Default")
      (node (ref "X-SOUTH") (pin "M2") (pinfunction "M2_M2") (pintype "bidirectional"))
    )
  )
)
